# aquam60.net
KiCad netlist of a schematic drawn in EAGLE
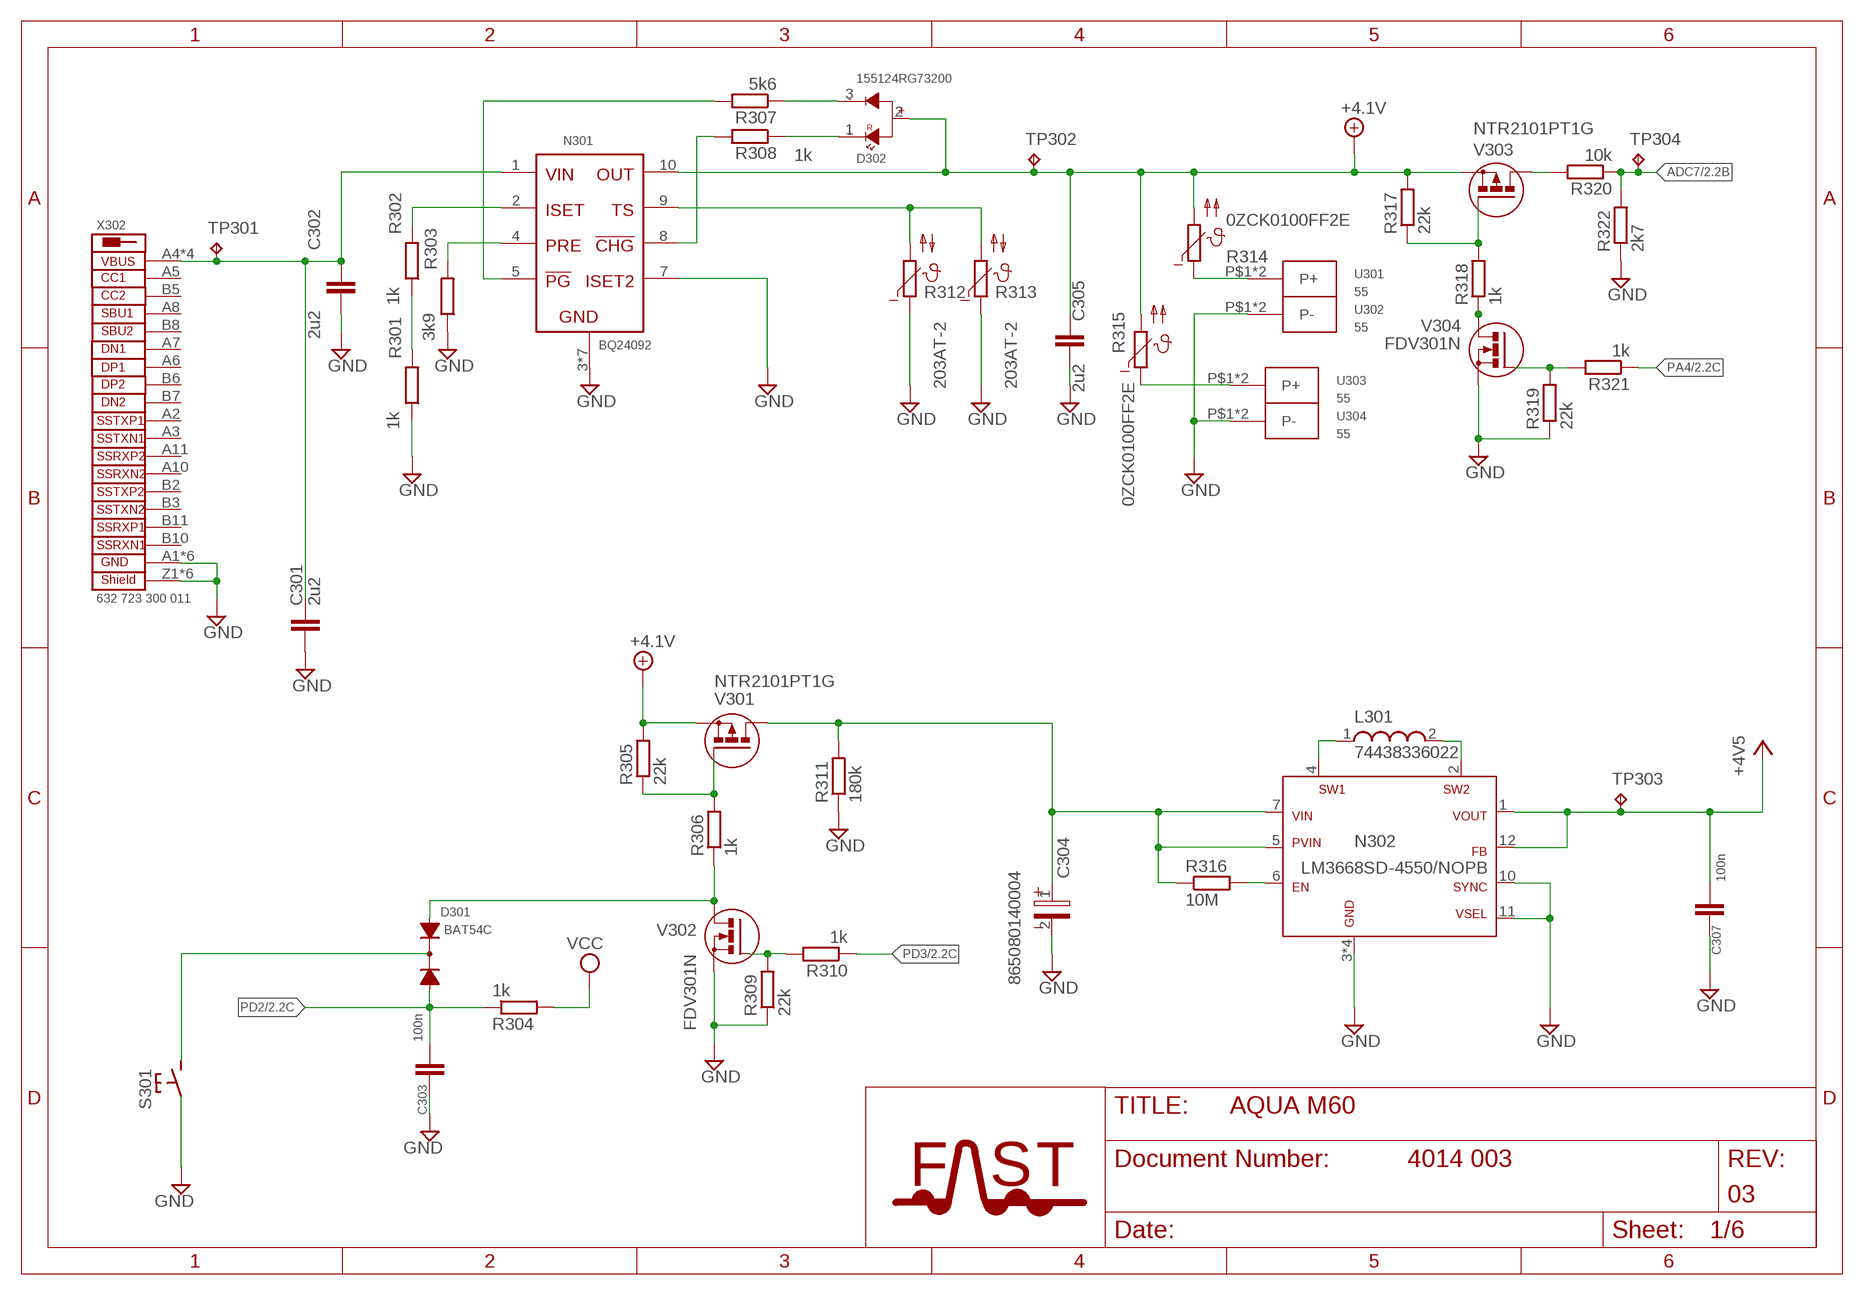
[diagram p0: schematic, sheet 1]
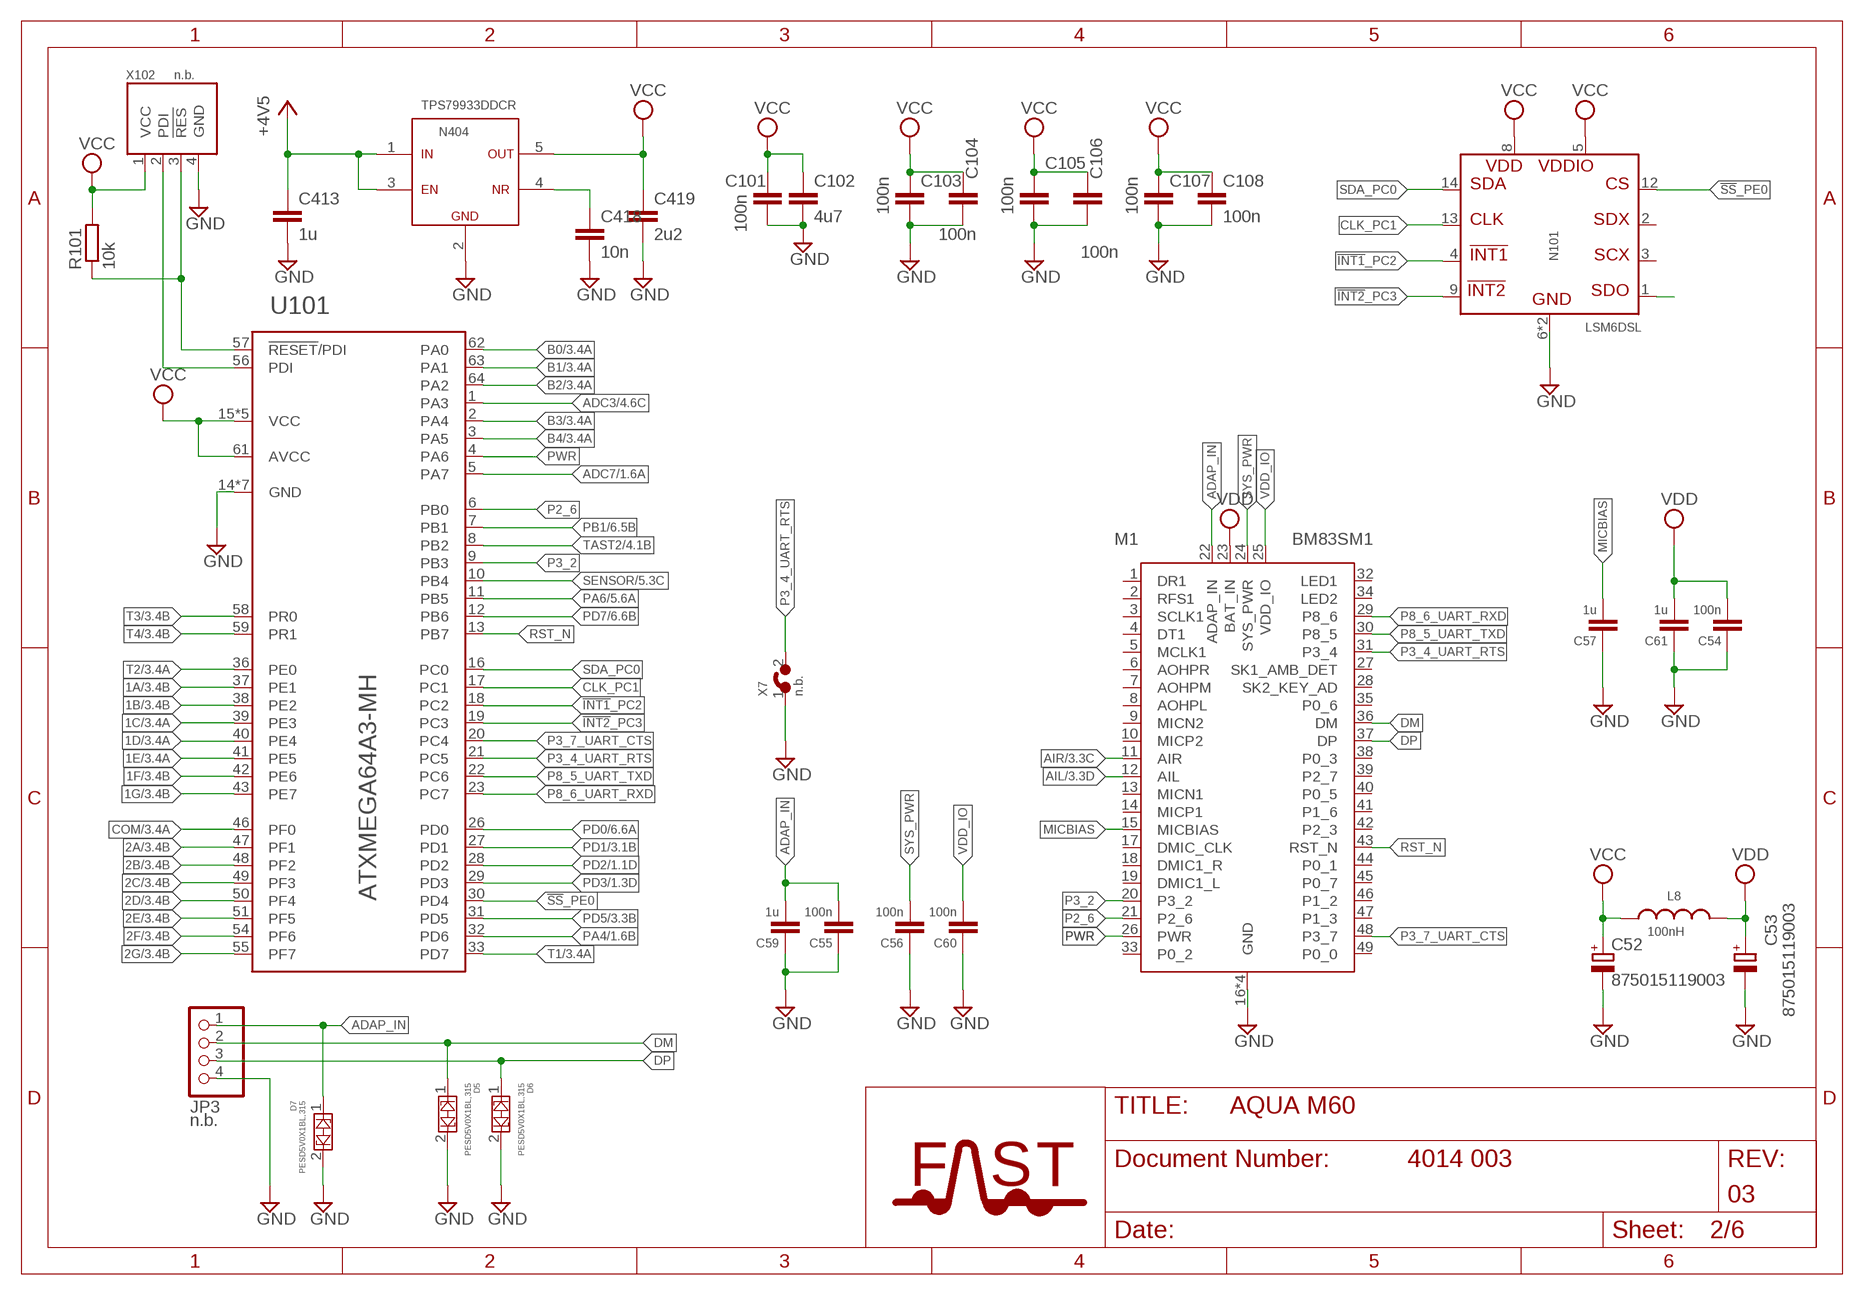
[diagram p1: schematic, sheet 2]
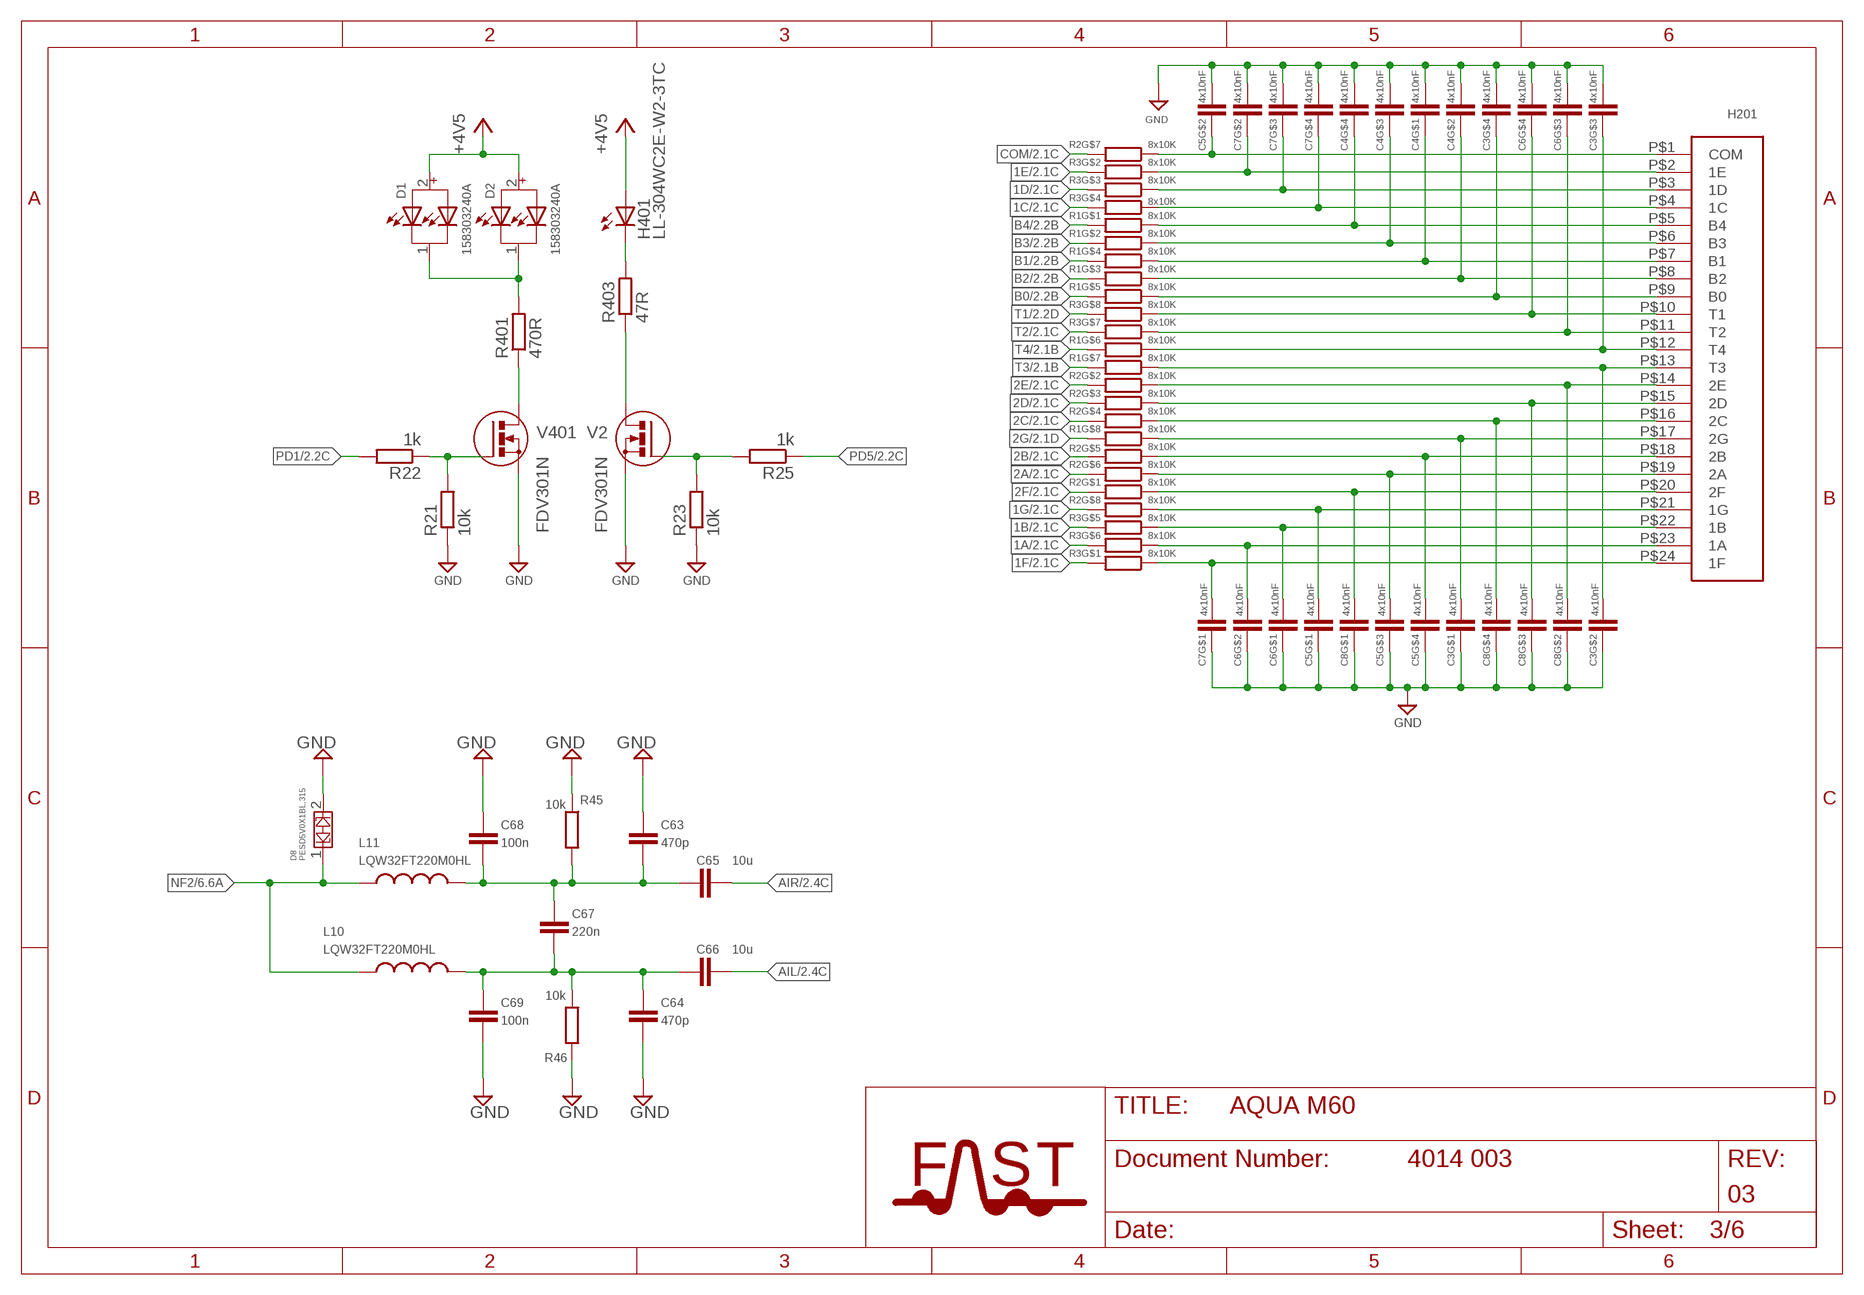
[diagram p2: schematic, sheet 3]
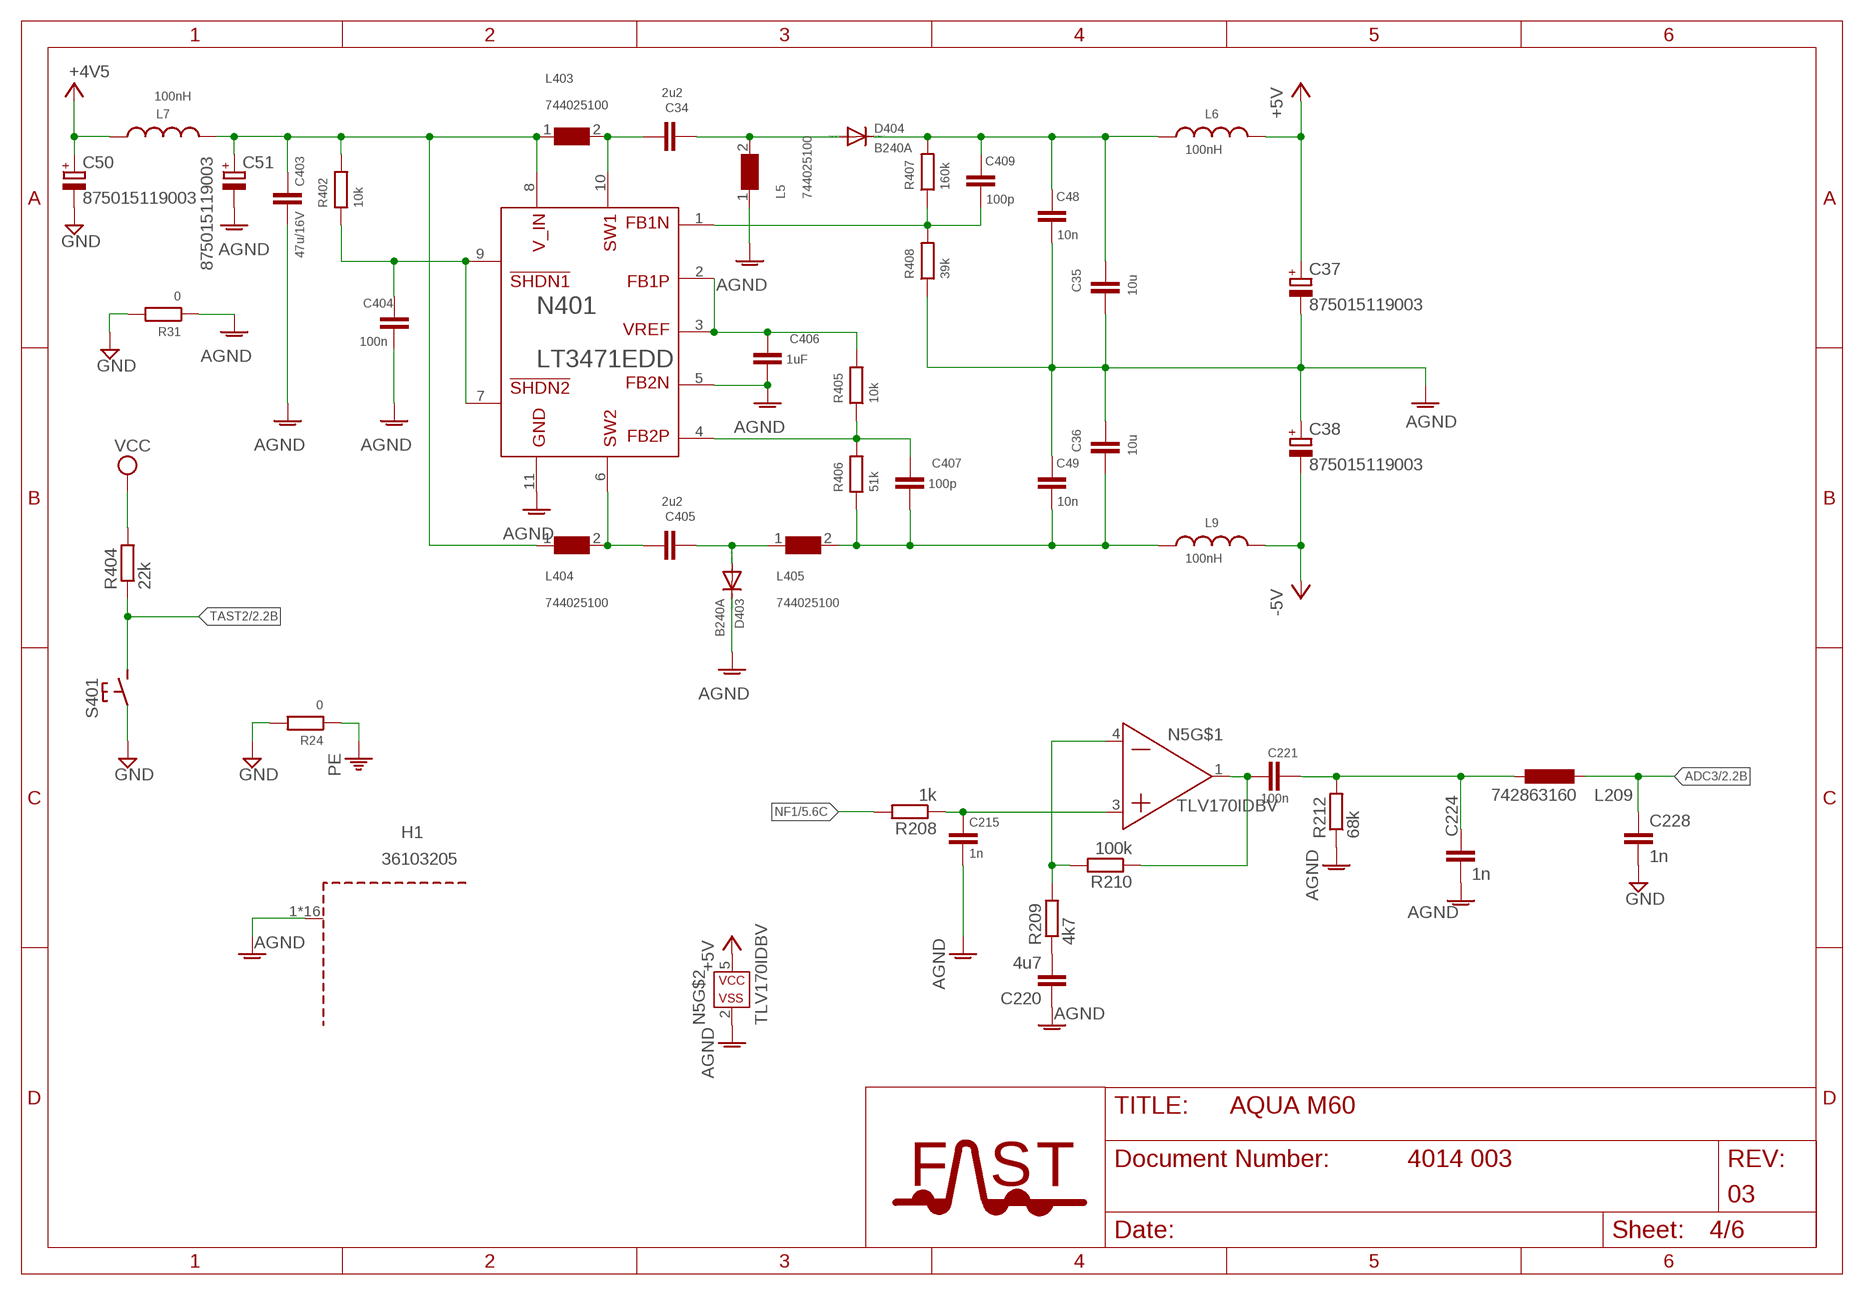
[diagram p3: schematic, sheet 4]
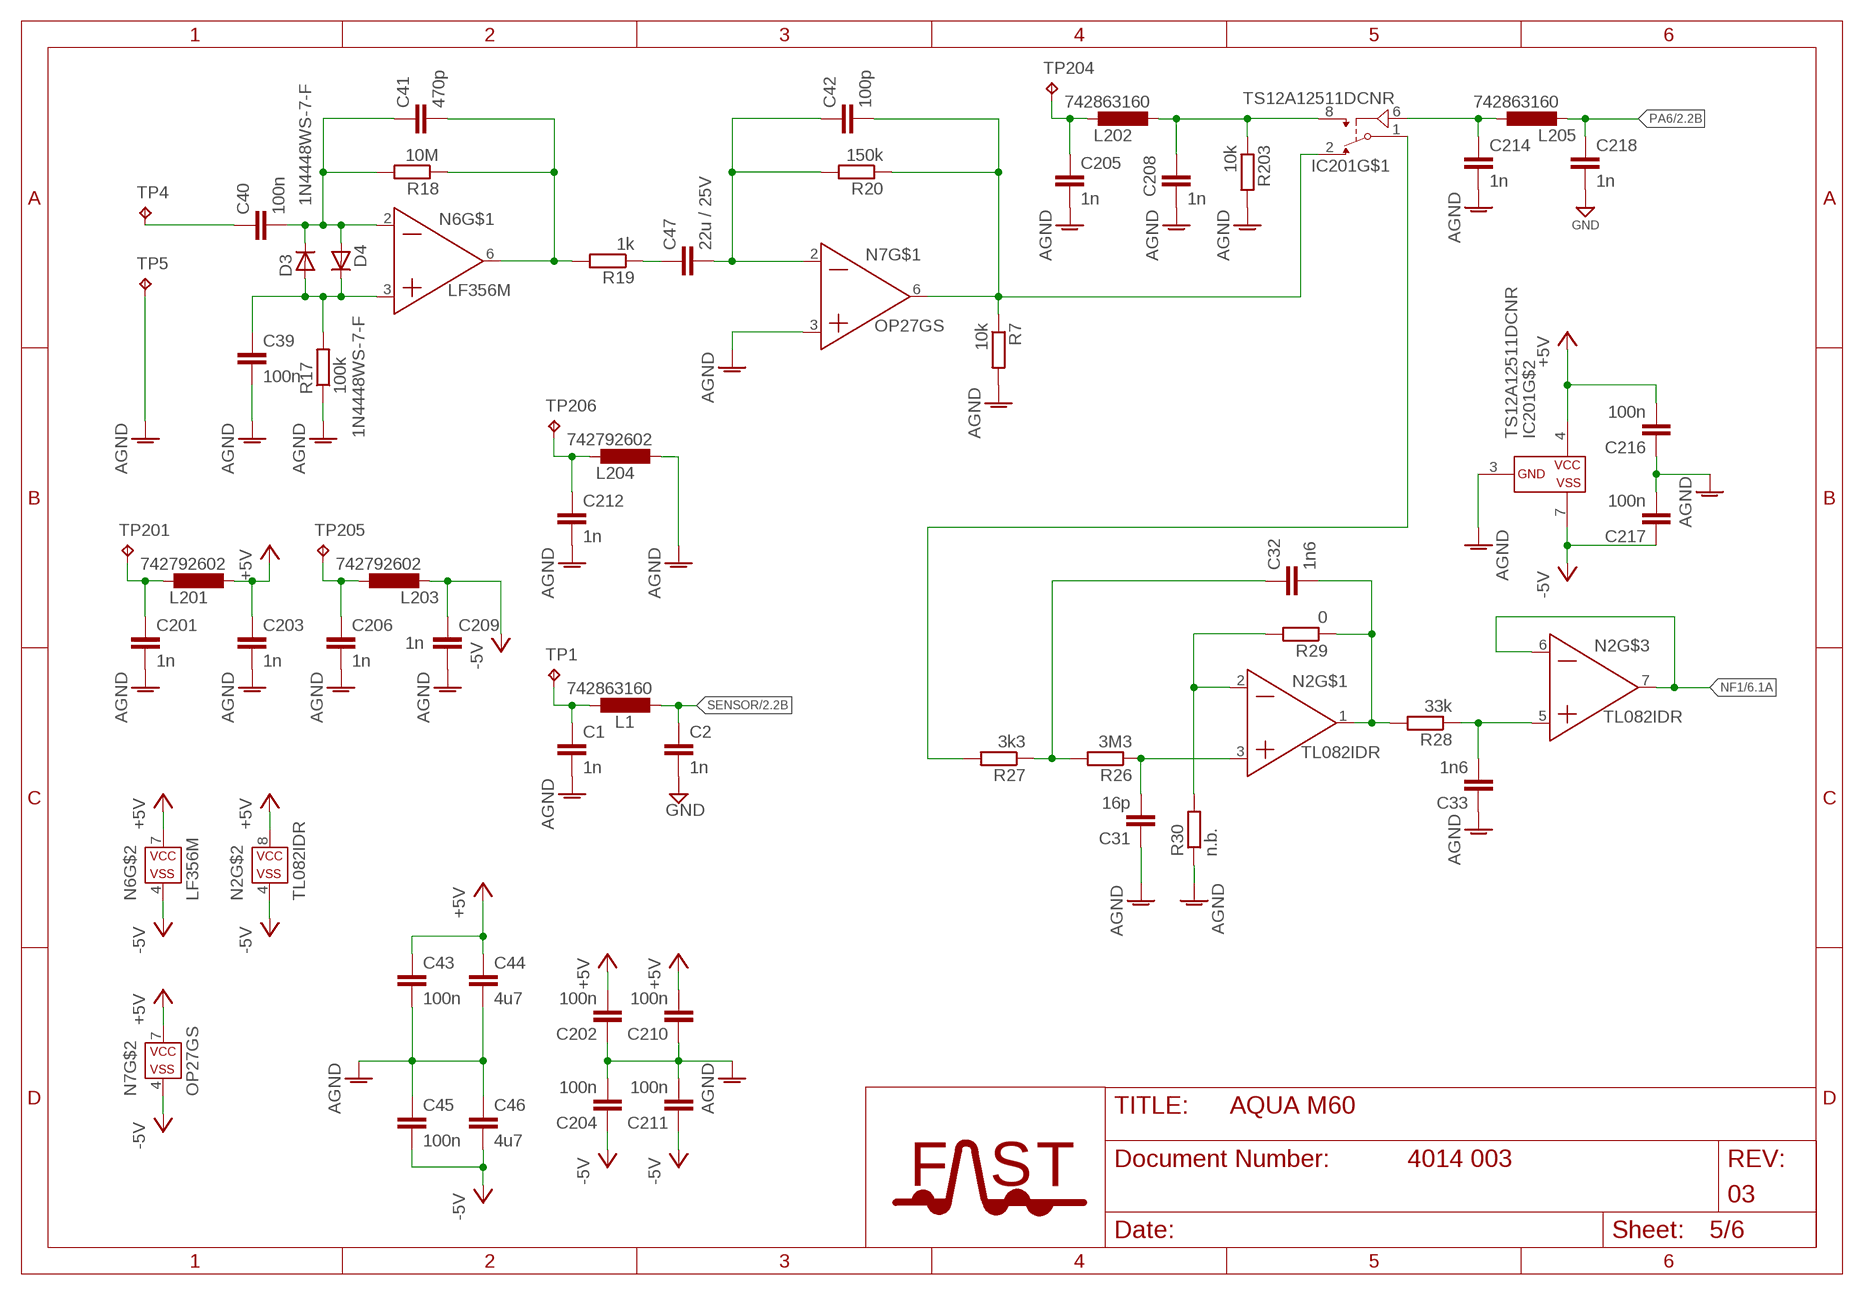
[diagram p4: schematic, sheet 5]
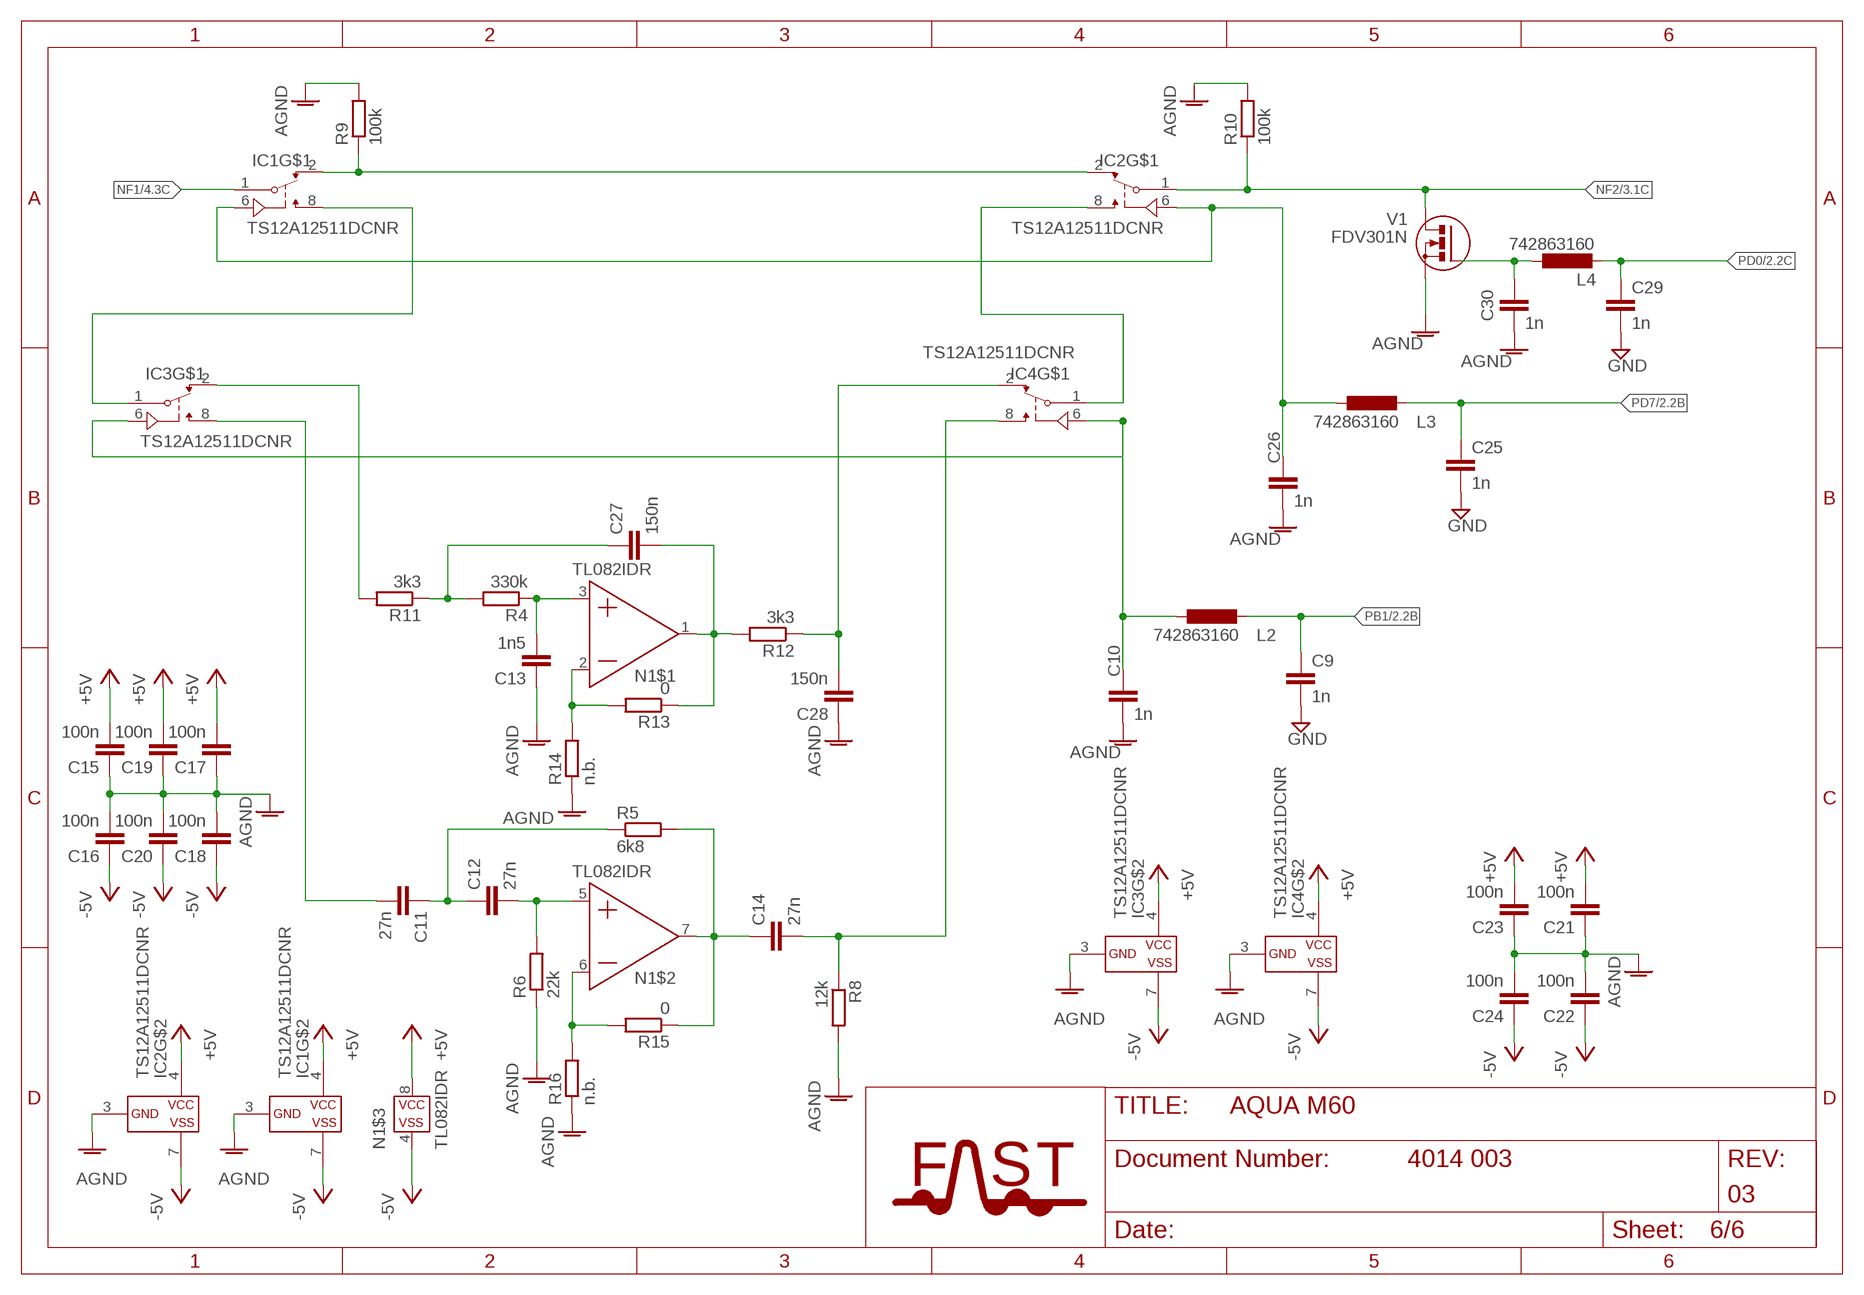
[diagram p5: schematic, sheet 6]

(export (version "E")
  (design (tool "Eeschema 10.0.6"))
  (components
    (comp (ref "C1")
      (value "1n")
      (footprint "eagle-import:C0603")
      (libsource (lib "eagle-import") (part "C-EUC0603"))
    )
    (comp (ref "C2")
      (value "1n")
      (footprint "eagle-import:C0603")
      (libsource (lib "eagle-import") (part "C-EUC0603"))
    )
    (comp (ref "C31")
      (value "16p")
      (footprint "eagle-import:C0603")
      (libsource (lib "eagle-import") (part "C-EUC0603"))
    )
    (comp (ref "C32")
      (value "1n6")
      (footprint "eagle-import:C0603")
      (libsource (lib "eagle-import") (part "C-EUC0603"))
    )
    (comp (ref "C33")
      (value "1n6")
      (footprint "eagle-import:C0603")
      (libsource (lib "eagle-import") (part "C-EUC0603"))
    )
    (comp (ref "C39")
      (value "100n")
      (footprint "eagle-import:C0805")
      (libsource (lib "eagle-import") (part "C-EUC0805"))
    )
    (comp (ref "C40")
      (value "100n")
      (footprint "eagle-import:C0805")
      (libsource (lib "eagle-import") (part "C-EUC0805"))
    )
    (comp (ref "C41")
      (value "470p")
      (footprint "eagle-import:C0805")
      (libsource (lib "eagle-import") (part "C-EUC0805"))
    )
    (comp (ref "C42")
      (value "100p")
      (footprint "eagle-import:C0805")
      (libsource (lib "eagle-import") (part "C-EUC0805"))
    )
    (comp (ref "C43")
      (value "100n")
      (footprint "eagle-import:C0603")
      (libsource (lib "eagle-import") (part "C-EUC0603"))
    )
    (comp (ref "C44")
      (value "4u7")
      (footprint "eagle-import:C0805")
      (libsource (lib "eagle-import") (part "C-EUC0805"))
    )
    (comp (ref "C45")
      (value "100n")
      (footprint "eagle-import:C0603")
      (libsource (lib "eagle-import") (part "C-EUC0603"))
    )
    (comp (ref "C46")
      (value "4u7")
      (footprint "eagle-import:C0805")
      (libsource (lib "eagle-import") (part "C-EUC0805"))
    )
    (comp (ref "C47")
      (value "22u / 25V")
      (footprint "eagle-import:C1210")
      (libsource (lib "eagle-import") (part "C-EUC1210"))
    )
    (comp (ref "C201")
      (value "1n")
      (footprint "eagle-import:C0603")
      (libsource (lib "eagle-import") (part "C-EUC0603"))
    )
    (comp (ref "C202")
      (value "100n")
      (footprint "eagle-import:C0603")
      (libsource (lib "eagle-import") (part "C-EUC0603"))
    )
    (comp (ref "C203")
      (value "1n")
      (footprint "eagle-import:C0603")
      (libsource (lib "eagle-import") (part "C-EUC0603"))
    )
    (comp (ref "C204")
      (value "100n")
      (footprint "eagle-import:C0603")
      (libsource (lib "eagle-import") (part "C-EUC0603"))
    )
    (comp (ref "C205")
      (value "1n")
      (footprint "eagle-import:C0603")
      (libsource (lib "eagle-import") (part "C-EUC0603"))
    )
    (comp (ref "C206")
      (value "1n")
      (footprint "eagle-import:C0603")
      (libsource (lib "eagle-import") (part "C-EUC0603"))
    )
    (comp (ref "C208")
      (value "1n")
      (footprint "eagle-import:C0603")
      (libsource (lib "eagle-import") (part "C-EUC0603"))
    )
    (comp (ref "C209")
      (value "1n")
      (footprint "eagle-import:C0603")
      (libsource (lib "eagle-import") (part "C-EUC0603"))
    )
    (comp (ref "C210")
      (value "100n")
      (footprint "eagle-import:C0603")
      (libsource (lib "eagle-import") (part "C-EUC0603"))
    )
    (comp (ref "C211")
      (value "100n")
      (footprint "eagle-import:C0603")
      (libsource (lib "eagle-import") (part "C-EUC0603"))
    )
    (comp (ref "C212")
      (value "1n")
      (footprint "eagle-import:C0603")
      (libsource (lib "eagle-import") (part "C-EUC0603"))
    )
    (comp (ref "C214")
      (value "1n")
      (footprint "eagle-import:C0603")
      (libsource (lib "eagle-import") (part "C-EUC0603"))
    )
    (comp (ref "C216")
      (value "100n")
      (footprint "eagle-import:C0603")
      (libsource (lib "eagle-import") (part "C-EUC0603"))
    )
    (comp (ref "C217")
      (value "100n")
      (footprint "eagle-import:C0603")
      (libsource (lib "eagle-import") (part "C-EUC0603"))
    )
    (comp (ref "C218")
      (value "1n")
      (footprint "eagle-import:C0603")
      (libsource (lib "eagle-import") (part "C-EUC0603"))
    )
    (comp (ref "D3")
      (value "1N4448WS-7-F")
      (footprint "eagle-import:SOD-323")
      (libsource (lib "eagle-import") (part "1N4448"))
    )
    (comp (ref "D4")
      (value "1N4448WS-7-F")
      (footprint "eagle-import:SOD-323")
      (libsource (lib "eagle-import") (part "1N4448"))
    )
    (comp (ref "IC201")
      (value "TS12A12511DCNR")
      (footprint "eagle-import:SOT-23-8")
      (libsource (lib "eagle-import") (part "TS12A12511DCN"))
    )
    (comp (ref "L1")
      (value "742863160")
      (footprint "eagle-import:R0603")
      (libsource (lib "eagle-import") (part "L-EUR0603"))
    )
    (comp (ref "L201")
      (value "742792602")
      (footprint "eagle-import:R0603")
      (libsource (lib "eagle-import") (part "L-EUR0603"))
    )
    (comp (ref "L202")
      (value "742863160")
      (footprint "eagle-import:R0603")
      (libsource (lib "eagle-import") (part "L-EUR0603"))
    )
    (comp (ref "L203")
      (value "742792602")
      (footprint "eagle-import:R0603")
      (libsource (lib "eagle-import") (part "L-EUR0603"))
    )
    (comp (ref "L204")
      (value "742792602")
      (footprint "eagle-import:R0603")
      (libsource (lib "eagle-import") (part "L-EUR0603"))
    )
    (comp (ref "L205")
      (value "742863160")
      (footprint "eagle-import:R0603")
      (libsource (lib "eagle-import") (part "L-EUR0603"))
    )
    (comp (ref "N2")
      (value "TL082IDR")
      (footprint "eagle-import:SO-8")
      (libsource (lib "eagle-import") (part "OPV_2"))
    )
    (comp (ref "N6")
      (value "LF356M")
      (footprint "eagle-import:SO-8")
      (libsource (lib "eagle-import") (part "OPV_1"))
    )
    (comp (ref "N7")
      (value "OP27GS")
      (footprint "eagle-import:SO-8")
      (libsource (lib "eagle-import") (part "OPV_1"))
    )
    (comp (ref "R7")
      (value "10k")
      (footprint "eagle-import:R0603")
      (libsource (lib "eagle-import") (part "R-EU_R0603"))
    )
    (comp (ref "R17")
      (value "100k")
      (footprint "eagle-import:R0805")
      (libsource (lib "eagle-import") (part "R-EU_R0805"))
    )
    (comp (ref "R18")
      (value "10M")
      (footprint "eagle-import:R0805")
      (libsource (lib "eagle-import") (part "R-EU_R0805"))
    )
    (comp (ref "R19")
      (value "1k")
      (footprint "eagle-import:R0805")
      (libsource (lib "eagle-import") (part "R-EU_R0805"))
    )
    (comp (ref "R20")
      (value "150k")
      (footprint "eagle-import:R0805")
      (libsource (lib "eagle-import") (part "R-EU_R0805"))
    )
    (comp (ref "R26")
      (value "3M3")
      (footprint "eagle-import:R0603")
      (libsource (lib "eagle-import") (part "R-EU_R0603"))
    )
    (comp (ref "R27")
      (value "3k3")
      (footprint "eagle-import:R0603")
      (libsource (lib "eagle-import") (part "R-EU_R0603"))
    )
    (comp (ref "R28")
      (value "33k")
      (footprint "eagle-import:R0603")
      (libsource (lib "eagle-import") (part "R-EU_R0603"))
    )
    (comp (ref "R29")
      (value "0")
      (footprint "eagle-import:R0603")
      (libsource (lib "eagle-import") (part "R-EU_R0603"))
    )
    (comp (ref "R30")
      (value "n.b.")
      (footprint "eagle-import:R0603")
      (libsource (lib "eagle-import") (part "R-EU_R0603"))
    )
    (comp (ref "R203")
      (value "10k")
      (footprint "eagle-import:R0603")
      (libsource (lib "eagle-import") (part "R-EU_R0603"))
    )
    (comp (ref "TP1")
      (value "n.b.")
      (footprint "eagle-import:P1-08")
      (libsource (lib "eagle-import") (part "TPB0,80"))
    )
    (comp (ref "TP4")
      (value "n.b.")
      (footprint "eagle-import:P1-13R")
      (libsource (lib "eagle-import") (part "TPPAD1-13R"))
    )
    (comp (ref "TP5")
      (value "n.b.")
      (footprint "eagle-import:P1-20")
      (libsource (lib "eagle-import") (part "TPPAD1-20"))
    )
    (comp (ref "TP201")
      (value "n.b.")
      (footprint "eagle-import:P1-08")
      (libsource (lib "eagle-import") (part "TPB0,80"))
    )
    (comp (ref "TP204")
      (value "n.b.")
      (footprint "eagle-import:P1-08")
      (libsource (lib "eagle-import") (part "TPB0,80"))
    )
    (comp (ref "TP205")
      (value "n.b.")
      (footprint "eagle-import:P1-08")
      (libsource (lib "eagle-import") (part "TPB0,80"))
    )
    (comp (ref "TP206")
      (value "n.b.")
      (footprint "eagle-import:P1-08")
      (libsource (lib "eagle-import") (part "TPB0,80"))
    )
    (comp (ref "C301")
      (value "2u2")
      (footprint "eagle-import:C0603")
      (libsource (lib "eagle-import") (part "C-EUC0603"))
    )
    (comp (ref "C302")
      (value "2u2")
      (footprint "eagle-import:C0603")
      (libsource (lib "eagle-import") (part "C-EUC0603"))
    )
    (comp (ref "C303")
      (value "100n")
      (footprint "eagle-import:C0603")
      (libsource (lib "eagle-import") (part "C-EUC0603"))
    )
    (comp (ref "C304")
      (value "865080140004")
      (footprint "eagle-import:2.6X1.6X1(BXCXA)")
      (libsource (lib "eagle-import") (part "WCAP-ASLI_4X5.5(DXL)"))
    )
    (comp (ref "C305")
      (value "2u2")
      (footprint "eagle-import:C0603")
      (libsource (lib "eagle-import") (part "C-EUC0603"))
    )
    (comp (ref "C307")
      (value "100n")
      (footprint "eagle-import:C0603")
      (libsource (lib "eagle-import") (part "C-EUC0603"))
    )
    (comp (ref "D301")
      (value "BAT54C")
      (footprint "eagle-import:SOT23")
      (libsource (lib "eagle-import") (part "BAT54C-1"))
    )
    (comp (ref "D302")
      (value "155124RG73200")
      (footprint "eagle-import:WL-SBSW_1204")
      (libsource (lib "eagle-import") (part "WL-SBSW_1204_155124RG73200"))
    )
    (comp (ref "L301")
      (value "74438336022")
      (footprint "eagle-import:WE-MAPI_3015_3020")
      (libsource (lib "eagle-import") (part "WE-MAPI_3015/3020_STANDER"))
    )
    (comp (ref "N301")
      (value "BQ24092")
      (footprint "eagle-import:HVSSOP10")
      (libsource (lib "eagle-import") (part "BQ2409X"))
    )
    (comp (ref "N302")
      (value "LM3668SD-4550/NOPB")
      (footprint "eagle-import:DFN_12POL_+0,2MM")
      (libsource (lib "eagle-import") (part "LM3668SD"))
    )
    (comp (ref "R301")
      (value "1k")
      (footprint "eagle-import:R0603")
      (libsource (lib "eagle-import") (part "R-EU_R0603"))
    )
    (comp (ref "R302")
      (value "1k")
      (footprint "eagle-import:R0603")
      (libsource (lib "eagle-import") (part "R-EU_R0603"))
    )
    (comp (ref "R303")
      (value "3k9")
      (footprint "eagle-import:R0603")
      (libsource (lib "eagle-import") (part "R-EU_R0603"))
    )
    (comp (ref "R304")
      (value "1k")
      (footprint "eagle-import:R0603")
      (libsource (lib "eagle-import") (part "R-EU_R0603"))
    )
    (comp (ref "R305")
      (value "22k")
      (footprint "eagle-import:R0603")
      (libsource (lib "eagle-import") (part "R-EU_R0603"))
    )
    (comp (ref "R306")
      (value "1k")
      (footprint "eagle-import:R0603")
      (libsource (lib "eagle-import") (part "R-EU_R0603"))
    )
    (comp (ref "R307")
      (value "5k6")
      (footprint "eagle-import:R0603")
      (libsource (lib "eagle-import") (part "R-EU_R0603"))
    )
    (comp (ref "R308")
      (value "1k")
      (footprint "eagle-import:R0603")
      (libsource (lib "eagle-import") (part "R-EU_R0603"))
    )
    (comp (ref "R309")
      (value "22k")
      (footprint "eagle-import:R0603")
      (libsource (lib "eagle-import") (part "R-EU_R0603"))
    )
    (comp (ref "R310")
      (value "1k")
      (footprint "eagle-import:R0603")
      (libsource (lib "eagle-import") (part "R-EU_R0603"))
    )
    (comp (ref "R311")
      (value "180k")
      (footprint "eagle-import:R0603")
      (libsource (lib "eagle-import") (part "R-EU_R0603"))
    )
    (comp (ref "R312")
      (value "203AT-2")
      (footprint "eagle-import:AT-2")
      (libsource (lib "eagle-import") (part "NTC"))
    )
    (comp (ref "R313")
      (value "203AT-2")
      (footprint "eagle-import:AT-2")
      (libsource (lib "eagle-import") (part "NTC"))
    )
    (comp (ref "R314")
      (value "0ZCK0100FF2E")
      (footprint "eagle-import:R0805")
      (libsource (lib "eagle-import") (part "PTC"))
    )
    (comp (ref "R315")
      (value "0ZCK0100FF2E")
      (footprint "eagle-import:R0805")
      (libsource (lib "eagle-import") (part "PTC"))
    )
    (comp (ref "R316")
      (value "10M")
      (footprint "eagle-import:R0603")
      (libsource (lib "eagle-import") (part "R-EU_R0603"))
    )
    (comp (ref "R317")
      (value "22k")
      (footprint "eagle-import:R0603")
      (libsource (lib "eagle-import") (part "R-EU_R0603"))
    )
    (comp (ref "R318")
      (value "1k")
      (footprint "eagle-import:R0603")
      (libsource (lib "eagle-import") (part "R-EU_R0603"))
    )
    (comp (ref "R319")
      (value "22k")
      (footprint "eagle-import:R0603")
      (libsource (lib "eagle-import") (part "R-EU_R0603"))
    )
    (comp (ref "R320")
      (value "10k")
      (footprint "eagle-import:R0603")
      (libsource (lib "eagle-import") (part "R-EU_R0603"))
    )
    (comp (ref "R321")
      (value "1k")
      (footprint "eagle-import:R0603")
      (libsource (lib "eagle-import") (part "R-EU_R0603"))
    )
    (comp (ref "R322")
      (value "2k7")
      (footprint "eagle-import:R0603")
      (libsource (lib "eagle-import") (part "R-EU_R0603"))
    )
    (comp (ref "S301")
      (value "1301.9320")
      (footprint "eagle-import:1301.93XX")
      (libsource (lib "eagle-import") (part "1301.93XX"))
    )
    (comp (ref "TP301")
      (value "n.b.")
      (footprint "eagle-import:TP10R")
      (libsource (lib "eagle-import") (part "TPTP10R"))
    )
    (comp (ref "TP302")
      (value "n.b.")
      (footprint "eagle-import:TP10R")
      (libsource (lib "eagle-import") (part "TPTP10R"))
    )
    (comp (ref "TP303")
      (value "n.b.")
      (footprint "eagle-import:TP10R")
      (libsource (lib "eagle-import") (part "TPTP10R"))
    )
    (comp (ref "TP304")
      (value "n.b.")
      (footprint "eagle-import:TP10R")
      (libsource (lib "eagle-import") (part "TPTP10R"))
    )
    (comp (ref "U301")
      (value "55")
      (footprint "eagle-import:55+")
      (libsource (lib "eagle-import") (part "55+"))
    )
    (comp (ref "U302")
      (value "55")
      (footprint "eagle-import:55-")
      (libsource (lib "eagle-import") (part "55--"))
    )
    (comp (ref "U303")
      (value "55")
      (footprint "eagle-import:55+")
      (libsource (lib "eagle-import") (part "55+"))
    )
    (comp (ref "U304")
      (value "55")
      (footprint "eagle-import:55-")
      (libsource (lib "eagle-import") (part "55--"))
    )
    (comp (ref "V301")
      (value "NTR2101PT1G")
      (footprint "eagle-import:SMDTR-1")
      (libsource (lib "eagle-import") (part "P-MOSFET-SOT23"))
    )
    (comp (ref "V302")
      (value "FDV301N")
      (footprint "eagle-import:SMDTR-1")
      (libsource (lib "eagle-import") (part "N-MOSFET-SOT23"))
    )
    (comp (ref "V303")
      (value "NTR2101PT1G")
      (footprint "eagle-import:SMDTR-1")
      (libsource (lib "eagle-import") (part "P-MOSFET-SOT23"))
    )
    (comp (ref "V304")
      (value "FDV301N")
      (footprint "eagle-import:SMDTR-1")
      (libsource (lib "eagle-import") (part "N-MOSFET-SOT23"))
    )
    (comp (ref "X302")
      (value "632 723 300 011")
      (footprint "eagle-import:632723300011_4L")
      (libsource (lib "eagle-import") (part "USB_3.1_TYPE_C_4L"))
    )
    (comp (ref "C3")
      (value "4x10nF")
      (footprint "eagle-import:C0612")
      (libsource (lib "eagle-import") (part "C_ARRAY_4X"))
    )
    (comp (ref "C4")
      (value "4x10nF")
      (footprint "eagle-import:C0612")
      (libsource (lib "eagle-import") (part "C_ARRAY_4X"))
    )
    (comp (ref "C5")
      (value "4x10nF")
      (footprint "eagle-import:C0612")
      (libsource (lib "eagle-import") (part "C_ARRAY_4X"))
    )
    (comp (ref "C6")
      (value "4x10nF")
      (footprint "eagle-import:C0612")
      (libsource (lib "eagle-import") (part "C_ARRAY_4X"))
    )
    (comp (ref "C7")
      (value "4x10nF")
      (footprint "eagle-import:C0612")
      (libsource (lib "eagle-import") (part "C_ARRAY_4X"))
    )
    (comp (ref "C8")
      (value "4x10nF")
      (footprint "eagle-import:C0612")
      (libsource (lib "eagle-import") (part "C_ARRAY_4X"))
    )
    (comp (ref "C63")
      (value "470p")
      (footprint "eagle-import:C0603")
      (libsource (lib "eagle-import") (part "C-EUC0603"))
    )
    (comp (ref "C64")
      (value "470p")
      (footprint "eagle-import:C0603")
      (libsource (lib "eagle-import") (part "C-EUC0603"))
    )
    (comp (ref "C65")
      (value "10u")
      (footprint "eagle-import:C0805")
      (libsource (lib "eagle-import") (part "C-EUC0805"))
    )
    (comp (ref "C66")
      (value "10u")
      (footprint "eagle-import:C0805")
      (libsource (lib "eagle-import") (part "C-EUC0805"))
    )
    (comp (ref "C67")
      (value "220n")
      (footprint "eagle-import:C0603")
      (libsource (lib "eagle-import") (part "C-EUC0603"))
    )
    (comp (ref "C68")
      (value "100n")
      (footprint "eagle-import:C0603")
      (libsource (lib "eagle-import") (part "C-EUC0603"))
    )
    (comp (ref "C69")
      (value "100n")
      (footprint "eagle-import:C0603")
      (libsource (lib "eagle-import") (part "C-EUC0603"))
    )
    (comp (ref "D1")
      (value "158303240A")
      (footprint "eagle-import:WL-SWTP_3030")
      (libsource (lib "eagle-import") (part "WL-SWTP_3030_158303240A"))
    )
    (comp (ref "D2")
      (value "158303240A")
      (footprint "eagle-import:WL-SWTP_3030")
      (libsource (lib "eagle-import") (part "WL-SWTP_3030_158303240A"))
    )
    (comp (ref "D8")
      (value "PESD5V0X1BL,315")
      (footprint "eagle-import:DIODFN100X60X60-2")
      (libsource (lib "eagle-import") (part "PESD5V0X1BL,315"))
    )
    (comp (ref "H201")
      (value "AQUAM60")
      (footprint "eagle-import:AQUAM60")
      (libsource (lib "eagle-import") (part "AQUAM60"))
    )
    (comp (ref "H401")
      (value "LL-304WC2E-W2-3TC")
      (footprint "eagle-import:LED3MM_H7,5MM")
      (libsource (lib "eagle-import") (part "LED"))
    )
    (comp (ref "L10")
      (value "LQW32FT220M0HL")
      (footprint "eagle-import:INDC3225X250N")
      (fields (field (name "MF") "Murata"))
      (libsource (lib "eagle-import") (part "LQW32FT220M0HL"))
    )
    (comp (ref "L11")
      (value "LQW32FT220M0HL")
      (footprint "eagle-import:INDC3225X250N")
      (fields (field (name "MF") "Murata"))
      (libsource (lib "eagle-import") (part "LQW32FT220M0HL"))
    )
    (comp (ref "R1")
      (value "8x10K")
      (footprint "eagle-import:R1506")
      (libsource (lib "eagle-import") (part "R_ARRAY_8X"))
    )
    (comp (ref "R2")
      (value "8x10K")
      (footprint "eagle-import:R1506")
      (libsource (lib "eagle-import") (part "R_ARRAY_8X"))
    )
    (comp (ref "R3")
      (value "8x10K")
      (footprint "eagle-import:R1506")
      (libsource (lib "eagle-import") (part "R_ARRAY_8X"))
    )
    (comp (ref "R21")
      (value "10k")
      (footprint "eagle-import:R0603")
      (libsource (lib "eagle-import") (part "R-EU_R0603"))
    )
    (comp (ref "R22")
      (value "1k")
      (footprint "eagle-import:R0603")
      (libsource (lib "eagle-import") (part "R-EU_R0603"))
    )
    (comp (ref "R23")
      (value "10k")
      (footprint "eagle-import:R0603")
      (libsource (lib "eagle-import") (part "R-EU_R0603"))
    )
    (comp (ref "R25")
      (value "1k")
      (footprint "eagle-import:R0603")
      (libsource (lib "eagle-import") (part "R-EU_R0603"))
    )
    (comp (ref "R45")
      (value "10k")
      (footprint "eagle-import:R0603")
      (libsource (lib "eagle-import") (part "R-EU_R0603"))
    )
    (comp (ref "R46")
      (value "10k")
      (footprint "eagle-import:R0603")
      (libsource (lib "eagle-import") (part "R-EU_R0603"))
    )
    (comp (ref "R401")
      (value "470R")
      (footprint "eagle-import:R0805")
      (libsource (lib "eagle-import") (part "R-EU_R0805"))
    )
    (comp (ref "R403")
      (value "47R")
      (footprint "eagle-import:R0805")
      (libsource (lib "eagle-import") (part "R-EU_R0805"))
    )
    (comp (ref "V2")
      (value "FDV301N")
      (footprint "eagle-import:SMDTR-1")
      (libsource (lib "eagle-import") (part "N-MOSFET-SOT23"))
    )
    (comp (ref "V401")
      (value "FDV301N")
      (footprint "eagle-import:SMDTR-1")
      (libsource (lib "eagle-import") (part "N-MOSFET-SOT23"))
    )
    (comp (ref "C9")
      (value "1n")
      (footprint "eagle-import:C0603")
      (libsource (lib "eagle-import") (part "C-EUC0603"))
    )
    (comp (ref "C10")
      (value "1n")
      (footprint "eagle-import:C0603")
      (libsource (lib "eagle-import") (part "C-EUC0603"))
    )
    (comp (ref "C11")
      (value "27n")
      (footprint "eagle-import:C0603")
      (libsource (lib "eagle-import") (part "C-EUC0603"))
    )
    (comp (ref "C12")
      (value "27n")
      (footprint "eagle-import:C0603")
      (libsource (lib "eagle-import") (part "C-EUC0603"))
    )
    (comp (ref "C13")
      (value "1n5")
      (footprint "eagle-import:C0603")
      (libsource (lib "eagle-import") (part "C-EUC0603"))
    )
    (comp (ref "C14")
      (value "27n")
      (footprint "eagle-import:C0603")
      (libsource (lib "eagle-import") (part "C-EUC0603"))
    )
    (comp (ref "C15")
      (value "100n")
      (footprint "eagle-import:C0603")
      (libsource (lib "eagle-import") (part "C-EUC0603"))
    )
    (comp (ref "C16")
      (value "100n")
      (footprint "eagle-import:C0603")
      (libsource (lib "eagle-import") (part "C-EUC0603"))
    )
    (comp (ref "C17")
      (value "100n")
      (footprint "eagle-import:C0603")
      (libsource (lib "eagle-import") (part "C-EUC0603"))
    )
    (comp (ref "C18")
      (value "100n")
      (footprint "eagle-import:C0603")
      (libsource (lib "eagle-import") (part "C-EUC0603"))
    )
    (comp (ref "C19")
      (value "100n")
      (footprint "eagle-import:C0603")
      (libsource (lib "eagle-import") (part "C-EUC0603"))
    )
    (comp (ref "C20")
      (value "100n")
      (footprint "eagle-import:C0603")
      (libsource (lib "eagle-import") (part "C-EUC0603"))
    )
    (comp (ref "C21")
      (value "100n")
      (footprint "eagle-import:C0603")
      (libsource (lib "eagle-import") (part "C-EUC0603"))
    )
    (comp (ref "C22")
      (value "100n")
      (footprint "eagle-import:C0603")
      (libsource (lib "eagle-import") (part "C-EUC0603"))
    )
    (comp (ref "C23")
      (value "100n")
      (footprint "eagle-import:C0603")
      (libsource (lib "eagle-import") (part "C-EUC0603"))
    )
    (comp (ref "C24")
      (value "100n")
      (footprint "eagle-import:C0603")
      (libsource (lib "eagle-import") (part "C-EUC0603"))
    )
    (comp (ref "C25")
      (value "1n")
      (footprint "eagle-import:C0603")
      (libsource (lib "eagle-import") (part "C-EUC0603"))
    )
    (comp (ref "C26")
      (value "1n")
      (footprint "eagle-import:C0603")
      (libsource (lib "eagle-import") (part "C-EUC0603"))
    )
    (comp (ref "C27")
      (value "150n")
      (footprint "eagle-import:C0603")
      (libsource (lib "eagle-import") (part "C-EUC0603"))
    )
    (comp (ref "C28")
      (value "150n")
      (footprint "eagle-import:C0603")
      (libsource (lib "eagle-import") (part "C-EUC0603"))
    )
    (comp (ref "C29")
      (value "1n")
      (footprint "eagle-import:C0603")
      (libsource (lib "eagle-import") (part "C-EUC0603"))
    )
    (comp (ref "C30")
      (value "1n")
      (footprint "eagle-import:C0603")
      (libsource (lib "eagle-import") (part "C-EUC0603"))
    )
    (comp (ref "IC1")
      (value "TS12A12511DCNR")
      (footprint "eagle-import:SOT-23-8")
      (libsource (lib "eagle-import") (part "TS12A12511DCN"))
    )
    (comp (ref "IC2")
      (value "TS12A12511DCNR")
      (footprint "eagle-import:SOT-23-8")
      (libsource (lib "eagle-import") (part "TS12A12511DCN"))
    )
    (comp (ref "IC3")
      (value "TS12A12511DCNR")
      (footprint "eagle-import:SOT-23-8")
      (libsource (lib "eagle-import") (part "TS12A12511DCN"))
    )
    (comp (ref "IC4")
      (value "TS12A12511DCNR")
      (footprint "eagle-import:SOT-23-8")
      (libsource (lib "eagle-import") (part "TS12A12511DCN"))
    )
    (comp (ref "L2")
      (value "742863160")
      (footprint "eagle-import:R0603")
      (libsource (lib "eagle-import") (part "L-EUR0603"))
    )
    (comp (ref "L3")
      (value "742863160")
      (footprint "eagle-import:R0603")
      (libsource (lib "eagle-import") (part "L-EUR0603"))
    )
    (comp (ref "L4")
      (value "742863160")
      (footprint "eagle-import:R0603")
      (libsource (lib "eagle-import") (part "L-EUR0603"))
    )
    (comp (ref "N1")
      (value "TL082IDR")
      (footprint "eagle-import:SO-8")
      (libsource (lib "eagle-import") (part "MCP6V02"))
    )
    (comp (ref "R4")
      (value "330k")
      (footprint "eagle-import:R0603")
      (libsource (lib "eagle-import") (part "R-EU_R0603"))
    )
    (comp (ref "R5")
      (value "6k8")
      (footprint "eagle-import:R0603")
      (libsource (lib "eagle-import") (part "R-EU_R0603"))
    )
    (comp (ref "R6")
      (value "22k")
      (footprint "eagle-import:R0603")
      (libsource (lib "eagle-import") (part "R-EU_R0603"))
    )
    (comp (ref "R8")
      (value "12k")
      (footprint "eagle-import:R0603")
      (libsource (lib "eagle-import") (part "R-EU_R0603"))
    )
    (comp (ref "R9")
      (value "100k")
      (footprint "eagle-import:R0603")
      (libsource (lib "eagle-import") (part "R-EU_R0603"))
    )
    (comp (ref "R10")
      (value "100k")
      (footprint "eagle-import:R0603")
      (libsource (lib "eagle-import") (part "R-EU_R0603"))
    )
    (comp (ref "R11")
      (value "3k3")
      (footprint "eagle-import:R0603")
      (libsource (lib "eagle-import") (part "R-EU_R0603"))
    )
    (comp (ref "R12")
      (value "3k3")
      (footprint "eagle-import:R0603")
      (libsource (lib "eagle-import") (part "R-EU_R0603"))
    )
    (comp (ref "R13")
      (value "0")
      (footprint "eagle-import:R0603")
      (libsource (lib "eagle-import") (part "R-EU_R0603"))
    )
    (comp (ref "R14")
      (value "n.b.")
      (footprint "eagle-import:R0603")
      (libsource (lib "eagle-import") (part "R-EU_R0603"))
    )
    (comp (ref "R15")
      (value "0")
      (footprint "eagle-import:R0603")
      (libsource (lib "eagle-import") (part "R-EU_R0603"))
    )
    (comp (ref "R16")
      (value "n.b.")
      (footprint "eagle-import:R0603")
      (libsource (lib "eagle-import") (part "R-EU_R0603"))
    )
    (comp (ref "V1")
      (value "FDV301N")
      (footprint "eagle-import:SMDTR-1")
      (libsource (lib "eagle-import") (part "N-MOSFET-SOT23"))
    )
    (comp (ref "C34")
      (value "2u2")
      (footprint "eagle-import:C0603")
      (libsource (lib "eagle-import") (part "C-EUC0603"))
    )
    (comp (ref "C35")
      (value "10u")
      (footprint "eagle-import:C1210")
      (libsource (lib "eagle-import") (part "C-EUC1210"))
    )
    (comp (ref "C36")
      (value "10u")
      (footprint "eagle-import:C1210")
      (libsource (lib "eagle-import") (part "C-EUC1210"))
    )
    (comp (ref "C37")
      (value "875015119003")
      (footprint "eagle-import:WE_WCAP-PHGP")
      (libsource (lib "eagle-import") (part "KONDENSATOR_WE_WCAP_PHET_7,3X4,3X1,9MM"))
    )
    (comp (ref "C38")
      (value "875015119003")
      (footprint "eagle-import:WE_WCAP-PHGP")
      (libsource (lib "eagle-import") (part "KONDENSATOR_WE_WCAP_PHET_7,3X4,3X1,9MM"))
    )
    (comp (ref "C48")
      (value "10n")
      (footprint "eagle-import:C0603")
      (libsource (lib "eagle-import") (part "C-EUC0603"))
    )
    (comp (ref "C49")
      (value "10n")
      (footprint "eagle-import:C0603")
      (libsource (lib "eagle-import") (part "C-EUC0603"))
    )
    (comp (ref "C50")
      (value "875015119003")
      (footprint "eagle-import:WE_WCAP-PHGP")
      (libsource (lib "eagle-import") (part "KONDENSATOR_WE_WCAP_PHET_7,3X4,3X1,9MM"))
    )
    (comp (ref "C51")
      (value "875015119003")
      (footprint "eagle-import:WE_WCAP-PHGP")
      (libsource (lib "eagle-import") (part "KONDENSATOR_WE_WCAP_PHET_7,3X4,3X1,9MM"))
    )
    (comp (ref "C215")
      (value "1n")
      (footprint "eagle-import:C0603")
      (libsource (lib "eagle-import") (part "C-EUC0603"))
    )
    (comp (ref "C220")
      (value "4u7")
      (footprint "eagle-import:C0805")
      (libsource (lib "eagle-import") (part "C-EUC0805"))
    )
    (comp (ref "C221")
      (value "100n")
      (footprint "eagle-import:C0805")
      (libsource (lib "eagle-import") (part "C-EUC0805"))
    )
    (comp (ref "C224")
      (value "1n")
      (footprint "eagle-import:C0603")
      (libsource (lib "eagle-import") (part "C-EUC0603"))
    )
    (comp (ref "C228")
      (value "1n")
      (footprint "eagle-import:C0603")
      (libsource (lib "eagle-import") (part "C-EUC0603"))
    )
    (comp (ref "C403")
      (value "47u/16V")
      (footprint "eagle-import:C1210")
      (libsource (lib "eagle-import") (part "C-EUC1210"))
    )
    (comp (ref "C404")
      (value "100n")
      (footprint "eagle-import:C0603")
      (libsource (lib "eagle-import") (part "C-EUC0603"))
    )
    (comp (ref "C405")
      (value "2u2")
      (footprint "eagle-import:C0603")
      (libsource (lib "eagle-import") (part "C-EUC0603"))
    )
    (comp (ref "C406")
      (value "1uF")
      (footprint "eagle-import:C0603")
      (libsource (lib "eagle-import") (part "C-EUC0603"))
    )
    (comp (ref "C407")
      (value "100p")
      (footprint "eagle-import:C0603")
      (libsource (lib "eagle-import") (part "C-EUC0603"))
    )
    (comp (ref "C409")
      (value "100p")
      (footprint "eagle-import:C0603")
      (libsource (lib "eagle-import") (part "C-EUC0603"))
    )
    (comp (ref "D403")
      (value "B240A")
      (footprint "eagle-import:DO214AC")
      (libsource (lib "eagle-import") (part "DIODE-DO214AC"))
    )
    (comp (ref "D404")
      (value "B240A")
      (footprint "eagle-import:DO214AC")
      (libsource (lib "eagle-import") (part "DIODE-DO214AC"))
    )
    (comp (ref "H1")
      (value "36103205")
      (footprint "eagle-import:WE-SHC_SMD-FRAME_36103205")
      (libsource (lib "eagle-import") (part "WE-SHC_SMD-FRAME_36103205"))
    )
    (comp (ref "L5")
      (value "744025100")
      (footprint "eagle-import:WE-TPC_2811_2813")
      (libsource (lib "eagle-import") (part "WE-TPC_2811/2813"))
    )
    (comp (ref "L6")
      (value "100nH")
      (footprint "eagle-import:WE-KI_0805")
      (libsource (lib "eagle-import") (part "WE-KI_0805_744760210A"))
    )
    (comp (ref "L7")
      (value "100nH")
      (footprint "eagle-import:WE-KI_0805")
      (libsource (lib "eagle-import") (part "WE-KI_0805_744760210A"))
    )
    (comp (ref "L9")
      (value "100nH")
      (footprint "eagle-import:WE-KI_0805")
      (libsource (lib "eagle-import") (part "WE-KI_0805_744760210A"))
    )
    (comp (ref "L209")
      (value "742863160")
      (footprint "eagle-import:R0603")
      (libsource (lib "eagle-import") (part "L-EUR0603"))
    )
    (comp (ref "L403")
      (value "744025100")
      (footprint "eagle-import:WE-TPC_2811_2813")
      (libsource (lib "eagle-import") (part "WE-TPC_2811/2813"))
    )
    (comp (ref "L404")
      (value "744025100")
      (footprint "eagle-import:WE-TPC_2811_2813")
      (libsource (lib "eagle-import") (part "WE-TPC_2811/2813"))
    )
    (comp (ref "L405")
      (value "744025100")
      (footprint "eagle-import:WE-TPC_2811_2813")
      (libsource (lib "eagle-import") (part "WE-TPC_2811/2813"))
    )
    (comp (ref "N5")
      (value "TLV170IDBV")
      (footprint "eagle-import:SOT-23L")
      (libsource (lib "eagle-import") (part "OPV_1SOT23-3"))
    )
    (comp (ref "N401")
      (value "LT3471EDD")
      (footprint "eagle-import:DFN_10POL_3X3MM+0,2MM")
      (fields (field (name "SPICEPREFIX") "X"))
      (libsource (lib "eagle-import") (part "LT3471"))
    )
    (comp (ref "R24")
      (value "0")
      (footprint "eagle-import:R0603")
      (libsource (lib "eagle-import") (part "R-EU_R0603"))
    )
    (comp (ref "R31")
      (value "0")
      (footprint "eagle-import:R0603")
      (libsource (lib "eagle-import") (part "R-EU_R0603"))
    )
    (comp (ref "R208")
      (value "1k")
      (footprint "eagle-import:R0603")
      (libsource (lib "eagle-import") (part "R-EU_R0603"))
    )
    (comp (ref "R209")
      (value "4k7")
      (footprint "eagle-import:R0603")
      (libsource (lib "eagle-import") (part "R-EU_R0603"))
    )
    (comp (ref "R210")
      (value "100k")
      (footprint "eagle-import:R0603")
      (libsource (lib "eagle-import") (part "R-EU_R0603"))
    )
    (comp (ref "R212")
      (value "68k")
      (footprint "eagle-import:R0603")
      (libsource (lib "eagle-import") (part "R-EU_R0603"))
    )
    (comp (ref "R402")
      (value "10k")
      (footprint "eagle-import:R0603")
      (libsource (lib "eagle-import") (part "R-EU_R0603"))
    )
    (comp (ref "R404")
      (value "22k")
      (footprint "eagle-import:R0603")
      (libsource (lib "eagle-import") (part "R-EU_R0603"))
    )
    (comp (ref "R405")
      (value "10k")
      (footprint "eagle-import:R0603")
      (libsource (lib "eagle-import") (part "R-EU_R0603"))
    )
    (comp (ref "R406")
      (value "51k")
      (footprint "eagle-import:R0603")
      (libsource (lib "eagle-import") (part "R-EU_R0603"))
    )
    (comp (ref "R407")
      (value "160k")
      (footprint "eagle-import:R0603")
      (libsource (lib "eagle-import") (part "R-EU_R0603"))
    )
    (comp (ref "R408")
      (value "39k")
      (footprint "eagle-import:R0603")
      (libsource (lib "eagle-import") (part "R-EU_R0603"))
    )
    (comp (ref "S401")
      (value "1301.9320")
      (footprint "eagle-import:1301.93XX")
      (libsource (lib "eagle-import") (part "1301.93XX"))
    )
    (comp (ref "C52")
      (value "875015119003")
      (footprint "eagle-import:WE_WCAP-PHGP")
      (libsource (lib "eagle-import") (part "KONDENSATOR_WE_WCAP_PHET_7,3X4,3X1,9MM"))
    )
    (comp (ref "C53")
      (value "875015119003")
      (footprint "eagle-import:WE_WCAP-PHGP")
      (libsource (lib "eagle-import") (part "KONDENSATOR_WE_WCAP_PHET_7,3X4,3X1,9MM"))
    )
    (comp (ref "C54")
      (value "100n")
      (footprint "eagle-import:C0603")
      (libsource (lib "eagle-import") (part "C-EUC0603"))
    )
    (comp (ref "C55")
      (value "100n")
      (footprint "eagle-import:C0603")
      (libsource (lib "eagle-import") (part "C-EUC0603"))
    )
    (comp (ref "C56")
      (value "100n")
      (footprint "eagle-import:C0603")
      (libsource (lib "eagle-import") (part "C-EUC0603"))
    )
    (comp (ref "C57")
      (value "1u")
      (footprint "eagle-import:C0603")
      (libsource (lib "eagle-import") (part "C-EUC0603"))
    )
    (comp (ref "C59")
      (value "1u")
      (footprint "eagle-import:C0603")
      (libsource (lib "eagle-import") (part "C-EUC0603"))
    )
    (comp (ref "C60")
      (value "100n")
      (footprint "eagle-import:C0603")
      (libsource (lib "eagle-import") (part "C-EUC0603"))
    )
    (comp (ref "C61")
      (value "1u")
      (footprint "eagle-import:C0603")
      (libsource (lib "eagle-import") (part "C-EUC0603"))
    )
    (comp (ref "C101")
      (value "100n")
      (footprint "eagle-import:C0603")
      (libsource (lib "eagle-import") (part "C-EUC0603"))
    )
    (comp (ref "C102")
      (value "4u7")
      (footprint "eagle-import:C0603")
      (libsource (lib "eagle-import") (part "C-EUC0603"))
    )
    (comp (ref "C103")
      (value "100n")
      (footprint "eagle-import:C0603")
      (libsource (lib "eagle-import") (part "C-EUC0603"))
    )
    (comp (ref "C104")
      (value "100n")
      (footprint "eagle-import:C0603")
      (libsource (lib "eagle-import") (part "C-EUC0603"))
    )
    (comp (ref "C105")
      (value "100n")
      (footprint "eagle-import:C0603")
      (libsource (lib "eagle-import") (part "C-EUC0603"))
    )
    (comp (ref "C106")
      (value "100n")
      (footprint "eagle-import:C0603")
      (libsource (lib "eagle-import") (part "C-EUC0603"))
    )
    (comp (ref "C107")
      (value "100n")
      (footprint "eagle-import:C0603")
      (libsource (lib "eagle-import") (part "C-EUC0603"))
    )
    (comp (ref "C108")
      (value "100n")
      (footprint "eagle-import:C0603")
      (libsource (lib "eagle-import") (part "C-EUC0603"))
    )
    (comp (ref "C413")
      (value "1u")
      (footprint "eagle-import:C0603")
      (libsource (lib "eagle-import") (part "C-EUC0603"))
    )
    (comp (ref "C418")
      (value "10n")
      (footprint "eagle-import:C0603")
      (libsource (lib "eagle-import") (part "C-EUC0603"))
    )
    (comp (ref "C419")
      (value "2u2")
      (footprint "eagle-import:C0603")
      (libsource (lib "eagle-import") (part "C-EUC0603"))
    )
    (comp (ref "D5")
      (value "PESD5V0X1BL,315")
      (footprint "eagle-import:DIODFN100X60X60-2")
      (libsource (lib "eagle-import") (part "PESD5V0X1BL,315"))
    )
    (comp (ref "D6")
      (value "PESD5V0X1BL,315")
      (footprint "eagle-import:DIODFN100X60X60-2")
      (libsource (lib "eagle-import") (part "PESD5V0X1BL,315"))
    )
    (comp (ref "D7")
      (value "PESD5V0X1BL,315")
      (footprint "eagle-import:DIODFN100X60X60-2")
      (libsource (lib "eagle-import") (part "PESD5V0X1BL,315"))
    )
    (comp (ref "JP3")
      (value "n.b.")
      (footprint "eagle-import:1X04")
      (libsource (lib "eagle-import") (part "PINHD-1X4"))
    )
    (comp (ref "L8")
      (value "100nH")
      (footprint "eagle-import:WE-KI_0805")
      (libsource (lib "eagle-import") (part "WE-KI_0805_744760210A"))
    )
    (comp (ref "M1")
      (value "BM83SM1")
      (footprint "eagle-import:BM83")
      (libsource (lib "eagle-import") (part "BM83"))
    )
    (comp (ref "N101")
      (value "LSM6DSL")
      (footprint "eagle-import:LGA-14")
      (libsource (lib "eagle-import") (part "LSM6DSLTR"))
    )
    (comp (ref "N404")
      (value "TPS79933DDCR")
      (footprint "eagle-import:SOT-23-5")
      (libsource (lib "eagle-import") (part "TPS79933"))
    )
    (comp (ref "R101")
      (value "10k")
      (footprint "eagle-import:R0603")
      (libsource (lib "eagle-import") (part "R-EU_R0603"))
    )
    (comp (ref "U101")
      (value "ATXMEGA64A3-MH")
      (footprint "eagle-import:MLF-(VQFN)-64M2-64")
      (libsource (lib "eagle-import") (part "ATXMEGA64A3-MH"))
    )
    (comp (ref "X7")
      (value "n.b.")
      (footprint "eagle-import:LöTBRüCKE_2")
      (libsource (lib "eagle-import") (part "LB1_2"))
    )
    (comp (ref "X102")
      (value "n.b.")
      (footprint "eagle-import:AVRPDI4")
      (libsource (lib "eagle-import") (part "AVRPDI"))
    )
  )
  (nets
    (net (code "1") (name "+4.1V") (class "Default")
      (node (ref "C305") (pin "1") (pinfunction "1_1") (pintype "passive"))
      (node (ref "D302") (pin "2") (pinfunction "2_2") (pintype "passive"))
      (node (ref "N301") (pin "10") (pinfunction "OUT_10") (pintype "power_in"))
      (node (ref "R305") (pin "2") (pinfunction "2_2") (pintype "passive"))
      (node (ref "R314") (pin "2") (pinfunction "2_2") (pintype "passive"))
      (node (ref "R315") (pin "2") (pinfunction "2_2") (pintype "passive"))
      (node (ref "R317") (pin "2") (pinfunction "2_2") (pintype "passive"))
      (node (ref "TP302") (pin "TP") (pinfunction "TP_TP") (pintype "input"))
      (node (ref "V301") (pin "2") (pinfunction "S_2") (pintype "passive"))
      (node (ref "V303") (pin "2") (pinfunction "S_2") (pintype "passive"))
    )
    (net (code "2") (name "+4V5") (class "Default")
      (node (ref "C307") (pin "2") (pinfunction "2_2") (pintype "passive"))
      (node (ref "C413") (pin "1") (pinfunction "1_1") (pintype "passive"))
      (node (ref "C50") (pin "2+") (pinfunction "+_2+") (pintype "passive"))
      (node (ref "D1") (pin "2") (pinfunction "+_2") (pintype "passive"))
      (node (ref "D2") (pin "2") (pinfunction "+_2") (pintype "passive"))
      (node (ref "H401") (pin "A") (pinfunction "A_A") (pintype "passive"))
      (node (ref "L7") (pin "1") (pinfunction "1_1") (pintype "passive"))
      (node (ref "N302") (pin "1") (pinfunction "VOUT_1") (pintype "bidirectional"))
      (node (ref "N302") (pin "12") (pinfunction "FB_12") (pintype "bidirectional"))
      (node (ref "N404") (pin "1") (pinfunction "IN_1") (pintype "power_in"))
      (node (ref "N404") (pin "3") (pinfunction "EN_3") (pintype "input"))
      (node (ref "TP303") (pin "TP") (pinfunction "TP_TP") (pintype "input"))
    )
    (net (code "3") (name "+5V") (class "Default")
      (node (ref "C15") (pin "2") (pinfunction "2_2") (pintype "passive"))
      (node (ref "C17") (pin "2") (pinfunction "2_2") (pintype "passive"))
      (node (ref "C19") (pin "2") (pinfunction "2_2") (pintype "passive"))
      (node (ref "C202") (pin "2") (pinfunction "2_2") (pintype "passive"))
      (node (ref "C203") (pin "1") (pinfunction "1_1") (pintype "passive"))
      (node (ref "C21") (pin "2") (pinfunction "2_2") (pintype "passive"))
      (node (ref "C210") (pin "2") (pinfunction "2_2") (pintype "passive"))
      (node (ref "C216") (pin "2") (pinfunction "2_2") (pintype "passive"))
      (node (ref "C23") (pin "2") (pinfunction "2_2") (pintype "passive"))
      (node (ref "C37") (pin "2+") (pinfunction "+_2+") (pintype "passive"))
      (node (ref "C43") (pin "1") (pinfunction "1_1") (pintype "passive"))
      (node (ref "C44") (pin "1") (pinfunction "1_1") (pintype "passive"))
      (node (ref "IC1") (pin "4") (pinfunction "VCC_4") (pintype "power_in"))
      (node (ref "IC2") (pin "4") (pinfunction "VCC_4") (pintype "power_in"))
      (node (ref "IC201") (pin "4") (pinfunction "VCC_4") (pintype "power_in"))
      (node (ref "IC3") (pin "4") (pinfunction "VCC_4") (pintype "power_in"))
      (node (ref "IC4") (pin "4") (pinfunction "VCC_4") (pintype "power_in"))
      (node (ref "L201") (pin "2") (pinfunction "2_2") (pintype "passive"))
      (node (ref "L6") (pin "2") (pinfunction "2_2") (pintype "passive"))
      (node (ref "N1") (pin "8") (pinfunction "VCC_8") (pintype "power_in"))
      (node (ref "N2") (pin "8") (pinfunction "VCC_8") (pintype "power_in"))
      (node (ref "N5") (pin "5") (pinfunction "VCC_5") (pintype "power_in"))
      (node (ref "N6") (pin "7") (pinfunction "VCC_7") (pintype "power_in"))
      (node (ref "N7") (pin "7") (pinfunction "VCC_7") (pintype "power_in"))
    )
    (net (code "4") (name "-5V") (class "Default")
      (node (ref "C16") (pin "1") (pinfunction "1_1") (pintype "passive"))
      (node (ref "C18") (pin "1") (pinfunction "1_1") (pintype "passive"))
      (node (ref "C20") (pin "1") (pinfunction "1_1") (pintype "passive"))
      (node (ref "C204") (pin "1") (pinfunction "1_1") (pintype "passive"))
      (node (ref "C209") (pin "1") (pinfunction "1_1") (pintype "passive"))
      (node (ref "C211") (pin "1") (pinfunction "1_1") (pintype "passive"))
      (node (ref "C217") (pin "1") (pinfunction "1_1") (pintype "passive"))
      (node (ref "C22") (pin "1") (pinfunction "1_1") (pintype "passive"))
      (node (ref "C24") (pin "1") (pinfunction "1_1") (pintype "passive"))
      (node (ref "C38") (pin "1-") (pinfunction "-_1-") (pintype "passive"))
      (node (ref "C45") (pin "2") (pinfunction "2_2") (pintype "passive"))
      (node (ref "C46") (pin "2") (pinfunction "2_2") (pintype "passive"))
      (node (ref "IC1") (pin "7") (pinfunction "VSS_7") (pintype "power_in"))
      (node (ref "IC2") (pin "7") (pinfunction "VSS_7") (pintype "power_in"))
      (node (ref "IC201") (pin "7") (pinfunction "VSS_7") (pintype "power_in"))
      (node (ref "IC3") (pin "7") (pinfunction "VSS_7") (pintype "power_in"))
      (node (ref "IC4") (pin "7") (pinfunction "VSS_7") (pintype "power_in"))
      (node (ref "L203") (pin "2") (pinfunction "2_2") (pintype "passive"))
      (node (ref "L9") (pin "2") (pinfunction "2_2") (pintype "passive"))
      (node (ref "N1") (pin "4") (pinfunction "VSS_4") (pintype "power_in"))
      (node (ref "N2") (pin "4") (pinfunction "VSS_4") (pintype "power_in"))
      (node (ref "N6") (pin "4") (pinfunction "VSS_4") (pintype "power_in"))
      (node (ref "N7") (pin "4") (pinfunction "VSS_4") (pintype "power_in"))
    )
    (net (code "5") (name "1A") (class "Default")
      (node (ref "R3") (pin "12") (pinfunction "2_12") (pintype "passive"))
      (node (ref "U101") (pin "37") (pinfunction "PE1_37") (pintype "bidirectional"))
    )
    (net (code "6") (name "1B") (class "Default")
      (node (ref "R3") (pin "10") (pinfunction "2_10") (pintype "passive"))
      (node (ref "U101") (pin "38") (pinfunction "PE2_38") (pintype "bidirectional"))
    )
    (net (code "7") (name "1C") (class "Default")
      (node (ref "R3") (pin "8") (pinfunction "2_8") (pintype "passive"))
      (node (ref "U101") (pin "39") (pinfunction "PE3_39") (pintype "bidirectional"))
    )
    (net (code "8") (name "1D") (class "Default")
      (node (ref "R3") (pin "6") (pinfunction "2_6") (pintype "passive"))
      (node (ref "U101") (pin "40") (pinfunction "PE4_40") (pintype "bidirectional"))
    )
    (net (code "9") (name "1E") (class "Default")
      (node (ref "R3") (pin "4") (pinfunction "2_4") (pintype "passive"))
      (node (ref "U101") (pin "41") (pinfunction "PE5_41") (pintype "bidirectional"))
    )
    (net (code "10") (name "1F") (class "Default")
      (node (ref "R3") (pin "2") (pinfunction "2_2") (pintype "passive"))
      (node (ref "U101") (pin "42") (pinfunction "PE6_42") (pintype "bidirectional"))
    )
    (net (code "11") (name "1G") (class "Default")
      (node (ref "R2") (pin "16") (pinfunction "2_16") (pintype "passive"))
      (node (ref "U101") (pin "43") (pinfunction "PE7_43") (pintype "bidirectional"))
    )
    (net (code "12") (name "2A") (class "Default")
      (node (ref "R2") (pin "12") (pinfunction "2_12") (pintype "passive"))
      (node (ref "U101") (pin "47") (pinfunction "PF1_47") (pintype "bidirectional"))
    )
    (net (code "13") (name "2B") (class "Default")
      (node (ref "R2") (pin "10") (pinfunction "2_10") (pintype "passive"))
      (node (ref "U101") (pin "48") (pinfunction "PF2_48") (pintype "bidirectional"))
    )
    (net (code "14") (name "2C") (class "Default")
      (node (ref "R2") (pin "8") (pinfunction "2_8") (pintype "passive"))
      (node (ref "U101") (pin "49") (pinfunction "PF3_49") (pintype "bidirectional"))
    )
    (net (code "15") (name "2D") (class "Default")
      (node (ref "R2") (pin "6") (pinfunction "2_6") (pintype "passive"))
      (node (ref "U101") (pin "50") (pinfunction "PF4_50") (pintype "bidirectional"))
    )
    (net (code "16") (name "2E") (class "Default")
      (node (ref "R2") (pin "4") (pinfunction "2_4") (pintype "passive"))
      (node (ref "U101") (pin "51") (pinfunction "PF5_51") (pintype "bidirectional"))
    )
    (net (code "17") (name "2F") (class "Default")
      (node (ref "R2") (pin "2") (pinfunction "2_2") (pintype "passive"))
      (node (ref "U101") (pin "54") (pinfunction "PF6_54") (pintype "bidirectional"))
    )
    (net (code "18") (name "2G") (class "Default")
      (node (ref "R1") (pin "16") (pinfunction "2_16") (pintype "passive"))
      (node (ref "U101") (pin "55") (pinfunction "PF7_55") (pintype "bidirectional"))
    )
    (net (code "19") (name "ADAP_IN") (class "Default")
      (node (ref "C55") (pin "2") (pinfunction "2_2") (pintype "passive"))
      (node (ref "C59") (pin "2") (pinfunction "2_2") (pintype "passive"))
      (node (ref "D7") (pin "1") (pinfunction "P$1_1") (pintype "bidirectional"))
      (node (ref "JP3") (pin "1") (pinfunction "1_1") (pintype "passive"))
      (node (ref "M1") (pin "22") (pinfunction "ADAP_IN_22") (pintype "power_in"))
    )
    (net (code "20") (name "ADC3") (class "Default")
      (node (ref "C228") (pin "1") (pinfunction "1_1") (pintype "passive"))
      (node (ref "L209") (pin "2") (pinfunction "2_2") (pintype "passive"))
      (node (ref "U101") (pin "1") (pinfunction "PA3_1") (pintype "bidirectional"))
    )
    (net (code "21") (name "ADC7") (class "Default")
      (node (ref "R320") (pin "1") (pinfunction "1_1") (pintype "passive"))
      (node (ref "R322") (pin "2") (pinfunction "2_2") (pintype "passive"))
      (node (ref "TP304") (pin "TP") (pinfunction "TP_TP") (pintype "input"))
      (node (ref "U101") (pin "5") (pinfunction "PA7_5") (pintype "bidirectional"))
    )
    (net (code "22") (name "AGND") (class "Default")
      (node (ref "C1") (pin "2") (pinfunction "2_2") (pintype "passive"))
      (node (ref "C10") (pin "2") (pinfunction "2_2") (pintype "passive"))
      (node (ref "C13") (pin "1") (pinfunction "1_1") (pintype "passive"))
      (node (ref "C15") (pin "1") (pinfunction "1_1") (pintype "passive"))
      (node (ref "C16") (pin "2") (pinfunction "2_2") (pintype "passive"))
      (node (ref "C17") (pin "1") (pinfunction "1_1") (pintype "passive"))
      (node (ref "C18") (pin "2") (pinfunction "2_2") (pintype "passive"))
      (node (ref "C19") (pin "1") (pinfunction "1_1") (pintype "passive"))
      (node (ref "C20") (pin "2") (pinfunction "2_2") (pintype "passive"))
      (node (ref "C201") (pin "2") (pinfunction "2_2") (pintype "passive"))
      (node (ref "C202") (pin "1") (pinfunction "1_1") (pintype "passive"))
      (node (ref "C203") (pin "2") (pinfunction "2_2") (pintype "passive"))
      (node (ref "C204") (pin "2") (pinfunction "2_2") (pintype "passive"))
      (node (ref "C205") (pin "2") (pinfunction "2_2") (pintype "passive"))
      (node (ref "C206") (pin "2") (pinfunction "2_2") (pintype "passive"))
      (node (ref "C208") (pin "2") (pinfunction "2_2") (pintype "passive"))
      (node (ref "C209") (pin "2") (pinfunction "2_2") (pintype "passive"))
      (node (ref "C21") (pin "1") (pinfunction "1_1") (pintype "passive"))
      (node (ref "C210") (pin "1") (pinfunction "1_1") (pintype "passive"))
      (node (ref "C211") (pin "2") (pinfunction "2_2") (pintype "passive"))
      (node (ref "C212") (pin "2") (pinfunction "2_2") (pintype "passive"))
      (node (ref "C214") (pin "2") (pinfunction "2_2") (pintype "passive"))
      (node (ref "C215") (pin "2") (pinfunction "2_2") (pintype "passive"))
      (node (ref "C216") (pin "1") (pinfunction "1_1") (pintype "passive"))
      (node (ref "C217") (pin "2") (pinfunction "2_2") (pintype "passive"))
      (node (ref "C22") (pin "2") (pinfunction "2_2") (pintype "passive"))
      (node (ref "C220") (pin "1") (pinfunction "1_1") (pintype "passive"))
      (node (ref "C224") (pin "2") (pinfunction "2_2") (pintype "passive"))
      (node (ref "C23") (pin "1") (pinfunction "1_1") (pintype "passive"))
      (node (ref "C24") (pin "2") (pinfunction "2_2") (pintype "passive"))
      (node (ref "C26") (pin "2") (pinfunction "2_2") (pintype "passive"))
      (node (ref "C28") (pin "1") (pinfunction "1_1") (pintype "passive"))
      (node (ref "C30") (pin "2") (pinfunction "2_2") (pintype "passive"))
      (node (ref "C31") (pin "1") (pinfunction "1_1") (pintype "passive"))
      (node (ref "C33") (pin "1") (pinfunction "1_1") (pintype "passive"))
      (node (ref "C35") (pin "2") (pinfunction "2_2") (pintype "passive"))
      (node (ref "C36") (pin "1") (pinfunction "1_1") (pintype "passive"))
      (node (ref "C37") (pin "1-") (pinfunction "-_1-") (pintype "passive"))
      (node (ref "C38") (pin "2+") (pinfunction "+_2+") (pintype "passive"))
      (node (ref "C39") (pin "2") (pinfunction "2_2") (pintype "passive"))
      (node (ref "C403") (pin "2") (pinfunction "2_2") (pintype "passive"))
      (node (ref "C404") (pin "2") (pinfunction "2_2") (pintype "passive"))
      (node (ref "C406") (pin "2") (pinfunction "2_2") (pintype "passive"))
      (node (ref "C43") (pin "2") (pinfunction "2_2") (pintype "passive"))
      (node (ref "C44") (pin "2") (pinfunction "2_2") (pintype "passive"))
      (node (ref "C45") (pin "1") (pinfunction "1_1") (pintype "passive"))
      (node (ref "C46") (pin "1") (pinfunction "1_1") (pintype "passive"))
      (node (ref "C48") (pin "2") (pinfunction "2_2") (pintype "passive"))
      (node (ref "C49") (pin "1") (pinfunction "1_1") (pintype "passive"))
      (node (ref "C51") (pin "1-") (pinfunction "-_1-") (pintype "passive"))
      (node (ref "D403") (pin "C") (pinfunction "C_C") (pintype "passive"))
      (node (ref "H1") (pin "1") (pinfunction "GND_1") (pintype "power_in"))
      (node (ref "H1") (pin "10") (pinfunction "GND_10") (pintype "power_in"))
      (node (ref "H1") (pin "11") (pinfunction "GND_11") (pintype "power_in"))
      (node (ref "H1") (pin "12") (pinfunction "GND_12") (pintype "power_in"))
      (node (ref "H1") (pin "13") (pinfunction "GND_13") (pintype "power_in"))
      (node (ref "H1") (pin "14") (pinfunction "GND_14") (pintype "power_in"))
      (node (ref "H1") (pin "15") (pinfunction "GND_15") (pintype "power_in"))
      (node (ref "H1") (pin "16") (pinfunction "GND_16") (pintype "power_in"))
      (node (ref "H1") (pin "2") (pinfunction "GND_2") (pintype "power_in"))
      (node (ref "H1") (pin "3") (pinfunction "GND_3") (pintype "power_in"))
      (node (ref "H1") (pin "4") (pinfunction "GND_4") (pintype "power_in"))
      (node (ref "H1") (pin "5") (pinfunction "GND_5") (pintype "power_in"))
      (node (ref "H1") (pin "6") (pinfunction "GND_6") (pintype "power_in"))
      (node (ref "H1") (pin "7") (pinfunction "GND_7") (pintype "power_in"))
      (node (ref "H1") (pin "8") (pinfunction "GND_8") (pintype "power_in"))
      (node (ref "H1") (pin "9") (pinfunction "GND_9") (pintype "power_in"))
      (node (ref "IC1") (pin "3") (pinfunction "GND_3") (pintype "power_in"))
      (node (ref "IC2") (pin "3") (pinfunction "GND_3") (pintype "power_in"))
      (node (ref "IC201") (pin "3") (pinfunction "GND_3") (pintype "power_in"))
      (node (ref "IC3") (pin "3") (pinfunction "GND_3") (pintype "power_in"))
      (node (ref "IC4") (pin "3") (pinfunction "GND_3") (pintype "power_in"))
      (node (ref "L204") (pin "2") (pinfunction "2_2") (pintype "passive"))
      (node (ref "L5") (pin "1") (pinfunction "1_1") (pintype "passive"))
      (node (ref "N401") (pin "11") (pinfunction "GND_11") (pintype "bidirectional"))
      (node (ref "N401") (pin "5") (pinfunction "FB2N_5") (pintype "bidirectional"))
      (node (ref "N5") (pin "2") (pinfunction "VSS_2") (pintype "power_in"))
      (node (ref "N7") (pin "3") (pinfunction "IN+_3") (pintype "input"))
      (node (ref "R10") (pin "2") (pinfunction "2_2") (pintype "passive"))
      (node (ref "R14") (pin "1") (pinfunction "1_1") (pintype "passive"))
      (node (ref "R16") (pin "1") (pinfunction "1_1") (pintype "passive"))
      (node (ref "R17") (pin "1") (pinfunction "1_1") (pintype "passive"))
      (node (ref "R203") (pin "2") (pinfunction "2_2") (pintype "passive"))
      (node (ref "R212") (pin "1") (pinfunction "1_1") (pintype "passive"))
      (node (ref "R30") (pin "1") (pinfunction "1_1") (pintype "passive"))
      (node (ref "R31") (pin "1") (pinfunction "1_1") (pintype "passive"))
      (node (ref "R408") (pin "1") (pinfunction "1_1") (pintype "passive"))
      (node (ref "R6") (pin "1") (pinfunction "1_1") (pintype "passive"))
      (node (ref "R7") (pin "2") (pinfunction "2_2") (pintype "passive"))
      (node (ref "R8") (pin "2") (pinfunction "2_2") (pintype "passive"))
      (node (ref "R9") (pin "2") (pinfunction "2_2") (pintype "passive"))
      (node (ref "TP5") (pin "TP") (pinfunction "TP_TP") (pintype "input"))
      (node (ref "V1") (pin "2") (pinfunction "S_2") (pintype "passive"))
    )
    (net (code "23") (name "AIL") (class "Default")
      (node (ref "C66") (pin "1") (pinfunction "1_1") (pintype "passive"))
      (node (ref "M1") (pin "12") (pinfunction "AIL_12") (pintype "input"))
    )
    (net (code "24") (name "AIR") (class "Default")
      (node (ref "C65") (pin "1") (pinfunction "1_1") (pintype "passive"))
      (node (ref "M1") (pin "11") (pinfunction "AIR_11") (pintype "input"))
    )
    (net (code "25") (name "B0") (class "Default")
      (node (ref "R1") (pin "10") (pinfunction "2_10") (pintype "passive"))
      (node (ref "U101") (pin "62") (pinfunction "PA0_62") (pintype "bidirectional"))
    )
    (net (code "26") (name "B1") (class "Default")
      (node (ref "R1") (pin "8") (pinfunction "2_8") (pintype "passive"))
      (node (ref "U101") (pin "63") (pinfunction "PA1_63") (pintype "bidirectional"))
    )
    (net (code "27") (name "B2") (class "Default")
      (node (ref "R1") (pin "6") (pinfunction "2_6") (pintype "passive"))
      (node (ref "U101") (pin "64") (pinfunction "PA2_64") (pintype "bidirectional"))
    )
    (net (code "28") (name "B3") (class "Default")
      (node (ref "R1") (pin "4") (pinfunction "2_4") (pintype "passive"))
      (node (ref "U101") (pin "2") (pinfunction "PA4_2") (pintype "bidirectional"))
    )
    (net (code "29") (name "B4") (class "Default")
      (node (ref "R1") (pin "2") (pinfunction "2_2") (pintype "passive"))
      (node (ref "U101") (pin "3") (pinfunction "PA5_3") (pintype "bidirectional"))
    )
    (net (code "30") (name "CLK_PC1") (class "Default")
      (node (ref "N101") (pin "13") (pinfunction "SCL_13") (pintype "input"))
      (node (ref "U101") (pin "17") (pinfunction "PC1_17") (pintype "bidirectional"))
    )
    (net (code "31") (name "COM") (class "Default")
      (node (ref "R2") (pin "14") (pinfunction "2_14") (pintype "passive"))
      (node (ref "U101") (pin "46") (pinfunction "PF0_46") (pintype "bidirectional"))
    )
    (net (code "32") (name "DM") (class "Default")
      (node (ref "D5") (pin "1") (pinfunction "P$1_1") (pintype "bidirectional"))
      (node (ref "JP3") (pin "2") (pinfunction "2_2") (pintype "passive"))
      (node (ref "M1") (pin "36") (pinfunction "DM_36") (pintype "bidirectional"))
    )
    (net (code "33") (name "DP") (class "Default")
      (node (ref "D6") (pin "1") (pinfunction "P$1_1") (pintype "bidirectional"))
      (node (ref "JP3") (pin "3") (pinfunction "3_3") (pintype "passive"))
      (node (ref "M1") (pin "37") (pinfunction "DP_37") (pintype "bidirectional"))
    )
    (net (code "34") (name "GND") (class "Default")
      (node (ref "C101") (pin "2") (pinfunction "2_2") (pintype "passive"))
      (node (ref "C102") (pin "2") (pinfunction "2_2") (pintype "passive"))
      (node (ref "C103") (pin "2") (pinfunction "2_2") (pintype "passive"))
      (node (ref "C104") (pin "2") (pinfunction "2_2") (pintype "passive"))
      (node (ref "C105") (pin "2") (pinfunction "2_2") (pintype "passive"))
      (node (ref "C106") (pin "2") (pinfunction "2_2") (pintype "passive"))
      (node (ref "C107") (pin "2") (pinfunction "2_2") (pintype "passive"))
      (node (ref "C108") (pin "2") (pinfunction "2_2") (pintype "passive"))
      (node (ref "C2") (pin "2") (pinfunction "2_2") (pintype "passive"))
      (node (ref "C218") (pin "2") (pinfunction "2_2") (pintype "passive"))
      (node (ref "C228") (pin "2") (pinfunction "2_2") (pintype "passive"))
      (node (ref "C25") (pin "2") (pinfunction "2_2") (pintype "passive"))
      (node (ref "C29") (pin "2") (pinfunction "2_2") (pintype "passive"))
      (node (ref "C3") (pin "2") (pinfunction "2_2") (pintype "passive"))
      (node (ref "C3") (pin "4") (pinfunction "2_4") (pintype "passive"))
      (node (ref "C3") (pin "6") (pinfunction "2_6") (pintype "passive"))
      (node (ref "C3") (pin "8") (pinfunction "2_8") (pintype "passive"))
      (node (ref "C301") (pin "2") (pinfunction "2_2") (pintype "passive"))
      (node (ref "C302") (pin "2") (pinfunction "2_2") (pintype "passive"))
      (node (ref "C303") (pin "1") (pinfunction "1_1") (pintype "passive"))
      (node (ref "C304") (pin "2") (pinfunction "2_2") (pintype "bidirectional"))
      (node (ref "C305") (pin "2") (pinfunction "2_2") (pintype "passive"))
      (node (ref "C307") (pin "1") (pinfunction "1_1") (pintype "passive"))
      (node (ref "C4") (pin "2") (pinfunction "2_2") (pintype "passive"))
      (node (ref "C4") (pin "4") (pinfunction "2_4") (pintype "passive"))
      (node (ref "C4") (pin "6") (pinfunction "2_6") (pintype "passive"))
      (node (ref "C4") (pin "8") (pinfunction "2_8") (pintype "passive"))
      (node (ref "C413") (pin "2") (pinfunction "2_2") (pintype "passive"))
      (node (ref "C418") (pin "2") (pinfunction "2_2") (pintype "passive"))
      (node (ref "C419") (pin "2") (pinfunction "2_2") (pintype "passive"))
      (node (ref "C5") (pin "2") (pinfunction "2_2") (pintype "passive"))
      (node (ref "C5") (pin "4") (pinfunction "2_4") (pintype "passive"))
      (node (ref "C5") (pin "6") (pinfunction "2_6") (pintype "passive"))
      (node (ref "C5") (pin "8") (pinfunction "2_8") (pintype "passive"))
      (node (ref "C50") (pin "1-") (pinfunction "-_1-") (pintype "passive"))
      (node (ref "C52") (pin "1-") (pinfunction "-_1-") (pintype "passive"))
      (node (ref "C53") (pin "1-") (pinfunction "-_1-") (pintype "passive"))
      (node (ref "C54") (pin "1") (pinfunction "1_1") (pintype "passive"))
      (node (ref "C55") (pin "1") (pinfunction "1_1") (pintype "passive"))
      (node (ref "C56") (pin "1") (pinfunction "1_1") (pintype "passive"))
      (node (ref "C57") (pin "1") (pinfunction "1_1") (pintype "passive"))
      (node (ref "C59") (pin "1") (pinfunction "1_1") (pintype "passive"))
      (node (ref "C6") (pin "1") (pinfunction "1_1") (pintype "passive"))
      (node (ref "C6") (pin "3") (pinfunction "1_3") (pintype "passive"))
      (node (ref "C6") (pin "5") (pinfunction "1_5") (pintype "passive"))
      (node (ref "C6") (pin "7") (pinfunction "1_7") (pintype "passive"))
      (node (ref "C60") (pin "1") (pinfunction "1_1") (pintype "passive"))
      (node (ref "C61") (pin "1") (pinfunction "1_1") (pintype "passive"))
      (node (ref "C63") (pin "2") (pinfunction "2_2") (pintype "passive"))
      (node (ref "C64") (pin "1") (pinfunction "1_1") (pintype "passive"))
      (node (ref "C68") (pin "2") (pinfunction "2_2") (pintype "passive"))
      (node (ref "C69") (pin "1") (pinfunction "1_1") (pintype "passive"))
      (node (ref "C7") (pin "1") (pinfunction "1_1") (pintype "passive"))
      (node (ref "C7") (pin "3") (pinfunction "1_3") (pintype "passive"))
      (node (ref "C7") (pin "5") (pinfunction "1_5") (pintype "passive"))
      (node (ref "C7") (pin "7") (pinfunction "1_7") (pintype "passive"))
      (node (ref "C8") (pin "1") (pinfunction "1_1") (pintype "passive"))
      (node (ref "C8") (pin "3") (pinfunction "1_3") (pintype "passive"))
      (node (ref "C8") (pin "5") (pinfunction "1_5") (pintype "passive"))
      (node (ref "C8") (pin "7") (pinfunction "1_7") (pintype "passive"))
      (node (ref "C9") (pin "2") (pinfunction "2_2") (pintype "passive"))
      (node (ref "D5") (pin "2") (pinfunction "P$2_2") (pintype "bidirectional"))
      (node (ref "D6") (pin "2") (pinfunction "P$2_2") (pintype "bidirectional"))
      (node (ref "D7") (pin "2") (pinfunction "P$2_2") (pintype "bidirectional"))
      (node (ref "D8") (pin "2") (pinfunction "P$2_2") (pintype "bidirectional"))
      (node (ref "JP3") (pin "4") (pinfunction "4_4") (pintype "passive"))
      (node (ref "M1") (pin "16") (pinfunction "GND_16") (pintype "power_in"))
      (node (ref "M1") (pin "50") (pinfunction "GND_50") (pintype "power_in"))
      (node (ref "M1") (pin "56") (pinfunction "GND_56") (pintype "power_in"))
      (node (ref "M1") (pin "57") (pinfunction "GND_57") (pintype "power_in"))
      (node (ref "N101") (pin "6") (pinfunction "GND_6") (pintype "power_in"))
      (node (ref "N101") (pin "7") (pinfunction "GND_7") (pintype "power_in"))
      (node (ref "N301") (pin "11") (pinfunction "GND_11") (pintype "power_in"))
      (node (ref "N301") (pin "3") (pinfunction "GND_3") (pintype "power_in"))
      (node (ref "N301") (pin "7") (pinfunction "ISET2_7") (pintype "input"))
      (node (ref "N301") (pin "P$1") (pinfunction "GND_P$1") (pintype "power_in"))
      (node (ref "N301") (pin "P$2") (pinfunction "GND_P$2") (pintype "power_in"))
      (node (ref "N301") (pin "P$3") (pinfunction "GND_P$3") (pintype "power_in"))
      (node (ref "N301") (pin "P$4") (pinfunction "GND_P$4") (pintype "power_in"))
      (node (ref "N301") (pin "P$5") (pinfunction "GND_P$5") (pintype "power_in"))
      (node (ref "N302") (pin "10") (pinfunction "SYNC_10") (pintype "bidirectional"))
      (node (ref "N302") (pin "11") (pinfunction "VSEL_11") (pintype "bidirectional"))
      (node (ref "N302") (pin "13") (pinfunction "GND_13") (pintype "bidirectional"))
      (node (ref "N302") (pin "3") (pinfunction "GND_3") (pintype "bidirectional"))
      (node (ref "N302") (pin "8") (pinfunction "GND_8") (pintype "bidirectional"))
      (node (ref "N302") (pin "9") (pinfunction "GND_9") (pintype "bidirectional"))
      (node (ref "N404") (pin "2") (pinfunction "GND_2") (pintype "power_in"))
      (node (ref "R21") (pin "1") (pinfunction "1_1") (pintype "passive"))
      (node (ref "R23") (pin "1") (pinfunction "1_1") (pintype "passive"))
      (node (ref "R24") (pin "2") (pinfunction "2_2") (pintype "passive"))
      (node (ref "R301") (pin "1") (pinfunction "1_1") (pintype "passive"))
      (node (ref "R303") (pin "1") (pinfunction "1_1") (pintype "passive"))
      (node (ref "R309") (pin "1") (pinfunction "1_1") (pintype "passive"))
      (node (ref "R31") (pin "2") (pinfunction "2_2") (pintype "passive"))
      (node (ref "R311") (pin "1") (pinfunction "1_1") (pintype "passive"))
      (node (ref "R312") (pin "P$1") (pinfunction "1_P$1") (pintype "passive"))
      (node (ref "R313") (pin "P$1") (pinfunction "1_P$1") (pintype "passive"))
      (node (ref "R319") (pin "1") (pinfunction "1_1") (pintype "passive"))
      (node (ref "R322") (pin "1") (pinfunction "1_1") (pintype "passive"))
      (node (ref "R45") (pin "1") (pinfunction "1_1") (pintype "passive"))
      (node (ref "R46") (pin "2") (pinfunction "2_2") (pintype "passive"))
      (node (ref "S301") (pin "P1") (pinfunction "1_P1") (pintype "bidirectional"))
      (node (ref "S301") (pin "P2") (pinfunction "1_P2") (pintype "bidirectional"))
      (node (ref "S401") (pin "P1") (pinfunction "1_P1") (pintype "bidirectional"))
      (node (ref "S401") (pin "P2") (pinfunction "1_P2") (pintype "bidirectional"))
      (node (ref "U101") (pin "14") (pinfunction "GND_14") (pintype "power_in"))
      (node (ref "U101") (pin "24") (pinfunction "GND_24") (pintype "power_in"))
      (node (ref "U101") (pin "34") (pinfunction "GND_34") (pintype "power_in"))
      (node (ref "U101") (pin "44") (pinfunction "GND_44") (pintype "power_in"))
      (node (ref "U101") (pin "52") (pinfunction "GND_52") (pintype "power_in"))
      (node (ref "U101") (pin "60") (pinfunction "GND_60") (pintype "power_in"))
      (node (ref "U101") (pin "TH") (pinfunction "GND_TH") (pintype "power_in"))
      (node (ref "U302") (pin "P$1") (pinfunction "P-_P$1") (pintype "bidirectional"))
      (node (ref "U302") (pin "P$2") (pinfunction "P-_P$2") (pintype "bidirectional"))
      (node (ref "U304") (pin "P$1") (pinfunction "P-_P$1") (pintype "bidirectional"))
      (node (ref "U304") (pin "P$2") (pinfunction "P-_P$2") (pintype "bidirectional"))
      (node (ref "V2") (pin "2") (pinfunction "S_2") (pintype "passive"))
      (node (ref "V302") (pin "2") (pinfunction "S_2") (pintype "passive"))
      (node (ref "V304") (pin "2") (pinfunction "S_2") (pintype "passive"))
      (node (ref "V401") (pin "2") (pinfunction "S_2") (pintype "passive"))
      (node (ref "X102") (pin "4") (pinfunction "GND_4") (pintype "passive"))
      (node (ref "X302") (pin "A1") (pinfunction "GND_A1") (pintype "bidirectional"))
      (node (ref "X302") (pin "A12") (pinfunction "GND_A12") (pintype "bidirectional"))
      (node (ref "X302") (pin "B1") (pinfunction "GND_B1") (pintype "bidirectional"))
      (node (ref "X302") (pin "B12") (pinfunction "GND_B12") (pintype "bidirectional"))
      (node (ref "X302") (pin "G3") (pinfunction "GND_G3") (pintype "bidirectional"))
      (node (ref "X302") (pin "G4") (pinfunction "GND_G4") (pintype "bidirectional"))
      (node (ref "X302") (pin "Z1") (pinfunction "SHIELD_Z1") (pintype "bidirectional"))
      (node (ref "X302") (pin "Z2") (pinfunction "SHIELD_Z2") (pintype "bidirectional"))
      (node (ref "X302") (pin "Z3") (pinfunction "SHIELD_Z3") (pintype "bidirectional"))
      (node (ref "X302") (pin "Z4") (pinfunction "SHIELD_Z4") (pintype "bidirectional"))
      (node (ref "X302") (pin "Z5") (pinfunction "SHIELD_Z5") (pintype "bidirectional"))
      (node (ref "X302") (pin "Z6") (pinfunction "SHIELD_Z6") (pintype "bidirectional"))
      (node (ref "X7") (pin "1") (pinfunction "IN_1") (pintype "bidirectional"))
    )
    (net (code "35") (name "MICBIAS") (class "Default")
      (node (ref "C57") (pin "2") (pinfunction "2_2") (pintype "passive"))
      (node (ref "M1") (pin "15") (pinfunction "MICBIAS_15") (pintype "power_in"))
    )
    (net (code "36") (name "NF1") (class "Default")
      (node (ref "IC1") (pin "1") (pinfunction "COM_1") (pintype "passive"))
      (node (ref "N2") (pin "6") (pinfunction "IN-_6") (pintype "input"))
      (node (ref "N2") (pin "7") (pinfunction "OUT_7") (pintype "output"))
      (node (ref "R208") (pin "2") (pinfunction "2_2") (pintype "passive"))
    )
    (net (code "37") (name "NF2") (class "Default")
      (node (ref "D8") (pin "1") (pinfunction "P$1_1") (pintype "bidirectional"))
      (node (ref "IC2") (pin "1") (pinfunction "COM_1") (pintype "passive"))
      (node (ref "L10") (pin "1") (pinfunction "1_1") (pintype "passive"))
      (node (ref "L11") (pin "1") (pinfunction "1_1") (pintype "passive"))
      (node (ref "R10") (pin "1") (pinfunction "1_1") (pintype "passive"))
      (node (ref "V1") (pin "3") (pinfunction "D_3") (pintype "passive"))
    )
    (net (code "38") (name "Net-(C1-Pad1)") (class "Default")
      (node (ref "C1") (pin "1") (pinfunction "1_1") (pintype "passive"))
      (node (ref "L1") (pin "1") (pinfunction "1_1") (pintype "passive"))
      (node (ref "TP1") (pin "TP") (pinfunction "TP_TP") (pintype "input"))
    )
    (net (code "39") (name "Net-(C3B-1)") (class "Default")
      (node (ref "C3") (pin "3") (pinfunction "1_3") (pintype "passive"))
      (node (ref "H201") (pin "P$13") (pinfunction "T3_P$13") (pintype "bidirectional"))
      (node (ref "R1") (pin "13") (pinfunction "1_13") (pintype "passive"))
    )
    (net (code "40") (name "Net-(C3C-1)") (class "Default")
      (node (ref "C3") (pin "5") (pinfunction "1_5") (pintype "passive"))
      (node (ref "H201") (pin "P$12") (pinfunction "T4_P$12") (pintype "bidirectional"))
      (node (ref "R1") (pin "11") (pinfunction "1_11") (pintype "passive"))
    )
    (net (code "41") (name "Net-(C3D-1)") (class "Default")
      (node (ref "C3") (pin "7") (pinfunction "1_7") (pintype "passive"))
      (node (ref "H201") (pin "P$9") (pinfunction "B0_P$9") (pintype "bidirectional"))
      (node (ref "R1") (pin "9") (pinfunction "1_9") (pintype "passive"))
    )
    (net (code "42") (name "Net-(C4B-1)") (class "Default")
      (node (ref "C4") (pin "3") (pinfunction "1_3") (pintype "passive"))
      (node (ref "H201") (pin "P$8") (pinfunction "B2_P$8") (pintype "bidirectional"))
      (node (ref "R1") (pin "5") (pinfunction "1_5") (pintype "passive"))
    )
    (net (code "43") (name "Net-(C4C-1)") (class "Default")
      (node (ref "C4") (pin "5") (pinfunction "1_5") (pintype "passive"))
      (node (ref "H201") (pin "P$6") (pinfunction "B3_P$6") (pintype "bidirectional"))
      (node (ref "R1") (pin "3") (pinfunction "1_3") (pintype "passive"))
    )
    (net (code "44") (name "Net-(C4D-1)") (class "Default")
      (node (ref "C4") (pin "7") (pinfunction "1_7") (pintype "passive"))
      (node (ref "H201") (pin "P$5") (pinfunction "B4_P$5") (pintype "bidirectional"))
      (node (ref "R1") (pin "1") (pinfunction "1_1") (pintype "passive"))
    )
    (net (code "45") (name "Net-(C5B-1)") (class "Default")
      (node (ref "C5") (pin "3") (pinfunction "1_3") (pintype "passive"))
      (node (ref "H201") (pin "P$1") (pinfunction "COM_P$1") (pintype "bidirectional"))
      (node (ref "R2") (pin "13") (pinfunction "1_13") (pintype "passive"))
    )
    (net (code "46") (name "Net-(C5C-1)") (class "Default")
      (node (ref "C5") (pin "5") (pinfunction "1_5") (pintype "passive"))
      (node (ref "H201") (pin "P$19") (pinfunction "2A_P$19") (pintype "bidirectional"))
      (node (ref "R2") (pin "11") (pinfunction "1_11") (pintype "passive"))
    )
    (net (code "47") (name "Net-(C5D-1)") (class "Default")
      (node (ref "C5") (pin "7") (pinfunction "1_7") (pintype "passive"))
      (node (ref "H201") (pin "P$18") (pinfunction "2B_P$18") (pintype "bidirectional"))
      (node (ref "R2") (pin "9") (pinfunction "1_9") (pintype "passive"))
    )
    (net (code "48") (name "Net-(C6B-2)") (class "Default")
      (node (ref "C6") (pin "4") (pinfunction "2_4") (pintype "passive"))
      (node (ref "H201") (pin "P$23") (pinfunction "1A_P$23") (pintype "bidirectional"))
      (node (ref "R3") (pin "11") (pinfunction "1_11") (pintype "passive"))
    )
    (net (code "49") (name "Net-(C6C-2)") (class "Default")
      (node (ref "C6") (pin "6") (pinfunction "2_6") (pintype "passive"))
      (node (ref "H201") (pin "P$11") (pinfunction "T2_P$11") (pintype "bidirectional"))
      (node (ref "R3") (pin "13") (pinfunction "1_13") (pintype "passive"))
    )
    (net (code "50") (name "Net-(C6D-2)") (class "Default")
      (node (ref "C6") (pin "8") (pinfunction "2_8") (pintype "passive"))
      (node (ref "H201") (pin "P$10") (pinfunction "T1_P$10") (pintype "bidirectional"))
      (node (ref "R3") (pin "15") (pinfunction "1_15") (pintype "passive"))
    )
    (net (code "51") (name "Net-(C7B-2)") (class "Default")
      (node (ref "C7") (pin "4") (pinfunction "2_4") (pintype "passive"))
      (node (ref "H201") (pin "P$2") (pinfunction "1E_P$2") (pintype "bidirectional"))
      (node (ref "R3") (pin "3") (pinfunction "1_3") (pintype "passive"))
    )
    (net (code "52") (name "Net-(C7C-2)") (class "Default")
      (node (ref "C7") (pin "6") (pinfunction "2_6") (pintype "passive"))
      (node (ref "H201") (pin "P$3") (pinfunction "1D_P$3") (pintype "bidirectional"))
      (node (ref "R3") (pin "5") (pinfunction "1_5") (pintype "passive"))
    )
    (net (code "53") (name "Net-(C7D-2)") (class "Default")
      (node (ref "C7") (pin "8") (pinfunction "2_8") (pintype "passive"))
      (node (ref "H201") (pin "P$4") (pinfunction "1C_P$4") (pintype "bidirectional"))
      (node (ref "R3") (pin "7") (pinfunction "1_7") (pintype "passive"))
    )
    (net (code "54") (name "Net-(C8B-2)") (class "Default")
      (node (ref "C8") (pin "4") (pinfunction "2_4") (pintype "passive"))
      (node (ref "H201") (pin "P$14") (pinfunction "2E_P$14") (pintype "bidirectional"))
      (node (ref "R2") (pin "3") (pinfunction "1_3") (pintype "passive"))
    )
    (net (code "55") (name "Net-(C8C-2)") (class "Default")
      (node (ref "C8") (pin "6") (pinfunction "2_6") (pintype "passive"))
      (node (ref "H201") (pin "P$15") (pinfunction "2D_P$15") (pintype "bidirectional"))
      (node (ref "R2") (pin "5") (pinfunction "1_5") (pintype "passive"))
    )
    (net (code "56") (name "Net-(C8D-2)") (class "Default")
      (node (ref "C8") (pin "8") (pinfunction "2_8") (pintype "passive"))
      (node (ref "H201") (pin "P$16") (pinfunction "2C_P$16") (pintype "bidirectional"))
      (node (ref "R2") (pin "7") (pinfunction "1_7") (pintype "passive"))
    )
    (net (code "57") (name "Net-(C11-Pad1)") (class "Default")
      (node (ref "C11") (pin "1") (pinfunction "1_1") (pintype "passive"))
      (node (ref "C12") (pin "1") (pinfunction "1_1") (pintype "passive"))
      (node (ref "R5") (pin "1") (pinfunction "1_1") (pintype "passive"))
    )
    (net (code "58") (name "Net-(C27-Pad1)") (class "Default")
      (node (ref "C27") (pin "1") (pinfunction "1_1") (pintype "passive"))
      (node (ref "R11") (pin "1") (pinfunction "1_1") (pintype "passive"))
      (node (ref "R4") (pin "2") (pinfunction "2_2") (pintype "passive"))
    )
    (net (code "59") (name "Net-(C32-Pad1)") (class "Default")
      (node (ref "C32") (pin "1") (pinfunction "1_1") (pintype "passive"))
      (node (ref "R26") (pin "2") (pinfunction "2_2") (pintype "passive"))
      (node (ref "R27") (pin "1") (pinfunction "1_1") (pintype "passive"))
    )
    (net (code "60") (name "Net-(C34-Pad1)") (class "Default")
      (node (ref "C34") (pin "1") (pinfunction "1_1") (pintype "passive"))
      (node (ref "D404") (pin "A") (pinfunction "A_A") (pintype "passive"))
      (node (ref "L5") (pin "2") (pinfunction "2_2") (pintype "passive"))
    )
    (net (code "61") (name "Net-(C35-Pad1)") (class "Default")
      (node (ref "C35") (pin "1") (pinfunction "1_1") (pintype "passive"))
      (node (ref "C409") (pin "1") (pinfunction "1_1") (pintype "passive"))
      (node (ref "C48") (pin "1") (pinfunction "1_1") (pintype "passive"))
      (node (ref "D404") (pin "C") (pinfunction "C_C") (pintype "passive"))
      (node (ref "L6") (pin "1") (pinfunction "1_1") (pintype "passive"))
      (node (ref "R407") (pin "2") (pinfunction "2_2") (pintype "passive"))
    )
    (net (code "62") (name "Net-(C36-Pad2)") (class "Default")
      (node (ref "C36") (pin "2") (pinfunction "2_2") (pintype "passive"))
      (node (ref "C407") (pin "2") (pinfunction "2_2") (pintype "passive"))
      (node (ref "C49") (pin "2") (pinfunction "2_2") (pintype "passive"))
      (node (ref "L405") (pin "2") (pinfunction "2_2") (pintype "passive"))
      (node (ref "L9") (pin "1") (pinfunction "1_1") (pintype "passive"))
      (node (ref "R406") (pin "1") (pinfunction "1_1") (pintype "passive"))
    )
    (net (code "63") (name "Net-(C40-Pad1)") (class "Default")
      (node (ref "C40") (pin "1") (pinfunction "1_1") (pintype "passive"))
      (node (ref "TP4") (pin "TP") (pinfunction "TP_TP") (pintype "input"))
    )
    (net (code "64") (name "Net-(C47-Pad1)") (class "Default")
      (node (ref "C47") (pin "1") (pinfunction "1_1") (pintype "passive"))
      (node (ref "R19") (pin "1") (pinfunction "1_1") (pintype "passive"))
    )
    (net (code "65") (name "Net-(C51-+)") (class "Default")
      (node (ref "C403") (pin "1") (pinfunction "1_1") (pintype "passive"))
      (node (ref "C51") (pin "2+") (pinfunction "+_2+") (pintype "passive"))
      (node (ref "L403") (pin "1") (pinfunction "1_1") (pintype "passive"))
      (node (ref "L404") (pin "1") (pinfunction "1_1") (pintype "passive"))
      (node (ref "L7") (pin "2") (pinfunction "2_2") (pintype "passive"))
      (node (ref "N401") (pin "8") (pinfunction "V_IN_8") (pintype "bidirectional"))
      (node (ref "R402") (pin "2") (pinfunction "2_2") (pintype "passive"))
    )
    (net (code "66") (name "Net-(C63-Pad1)") (class "Default")
      (node (ref "C63") (pin "1") (pinfunction "1_1") (pintype "passive"))
      (node (ref "C65") (pin "2") (pinfunction "2_2") (pintype "passive"))
      (node (ref "C67") (pin "2") (pinfunction "2_2") (pintype "passive"))
      (node (ref "C68") (pin "1") (pinfunction "1_1") (pintype "passive"))
      (node (ref "L11") (pin "2") (pinfunction "2_2") (pintype "passive"))
      (node (ref "R45") (pin "2") (pinfunction "2_2") (pintype "passive"))
    )
    (net (code "67") (name "Net-(C64-Pad2)") (class "Default")
      (node (ref "C64") (pin "2") (pinfunction "2_2") (pintype "passive"))
      (node (ref "C66") (pin "2") (pinfunction "2_2") (pintype "passive"))
      (node (ref "C67") (pin "1") (pinfunction "1_1") (pintype "passive"))
      (node (ref "C69") (pin "2") (pinfunction "2_2") (pintype "passive"))
      (node (ref "L10") (pin "2") (pinfunction "2_2") (pintype "passive"))
      (node (ref "R46") (pin "1") (pinfunction "1_1") (pintype "passive"))
    )
    (net (code "68") (name "Net-(C201-Pad1)") (class "Default")
      (node (ref "C201") (pin "1") (pinfunction "1_1") (pintype "passive"))
      (node (ref "L201") (pin "1") (pinfunction "1_1") (pintype "passive"))
      (node (ref "TP201") (pin "TP") (pinfunction "TP_TP") (pintype "input"))
    )
    (net (code "69") (name "Net-(C205-Pad1)") (class "Default")
      (node (ref "C205") (pin "1") (pinfunction "1_1") (pintype "passive"))
      (node (ref "L202") (pin "1") (pinfunction "1_1") (pintype "passive"))
      (node (ref "TP204") (pin "TP") (pinfunction "TP_TP") (pintype "input"))
    )
    (net (code "70") (name "Net-(C206-Pad1)") (class "Default")
      (node (ref "C206") (pin "1") (pinfunction "1_1") (pintype "passive"))
      (node (ref "L203") (pin "1") (pinfunction "1_1") (pintype "passive"))
      (node (ref "TP205") (pin "TP") (pinfunction "TP_TP") (pintype "input"))
    )
    (net (code "71") (name "Net-(C212-Pad1)") (class "Default")
      (node (ref "C212") (pin "1") (pinfunction "1_1") (pintype "passive"))
      (node (ref "L204") (pin "1") (pinfunction "1_1") (pintype "passive"))
      (node (ref "TP206") (pin "TP") (pinfunction "TP_TP") (pintype "input"))
    )
    (net (code "72") (name "Net-(C220-Pad2)") (class "Default")
      (node (ref "C220") (pin "2") (pinfunction "2_2") (pintype "passive"))
      (node (ref "R209") (pin "1") (pinfunction "1_1") (pintype "passive"))
    )
    (net (code "73") (name "Net-(C221-Pad1)") (class "Default")
      (node (ref "C221") (pin "1") (pinfunction "1_1") (pintype "passive"))
      (node (ref "C224") (pin "1") (pinfunction "1_1") (pintype "passive"))
      (node (ref "L209") (pin "1") (pinfunction "1_1") (pintype "passive"))
      (node (ref "R212") (pin "2") (pinfunction "2_2") (pintype "passive"))
    )
    (net (code "74") (name "Net-(C405-Pad1)") (class "Default")
      (node (ref "C405") (pin "1") (pinfunction "1_1") (pintype "passive"))
      (node (ref "D403") (pin "A") (pinfunction "A_A") (pintype "passive"))
      (node (ref "L405") (pin "1") (pinfunction "1_1") (pintype "passive"))
    )
    (net (code "75") (name "Net-(D1--)") (class "Default")
      (node (ref "D1") (pin "1") (pinfunction "-_1") (pintype "passive"))
      (node (ref "D2") (pin "1") (pinfunction "-_1") (pintype "passive"))
      (node (ref "R401") (pin "2") (pinfunction "2_2") (pintype "passive"))
    )
    (net (code "76") (name "Net-(D3-C)") (class "Default")
      (node (ref "C40") (pin "2") (pinfunction "2_2") (pintype "passive"))
      (node (ref "C41") (pin "1") (pinfunction "1_1") (pintype "passive"))
      (node (ref "D3") (pin "K") (pinfunction "C_K") (pintype "passive"))
      (node (ref "D4") (pin "A") (pinfunction "A_A") (pintype "passive"))
      (node (ref "N6") (pin "2") (pinfunction "IN-_2") (pintype "input"))
      (node (ref "R18") (pin "2") (pinfunction "2_2") (pintype "passive"))
    )
    (net (code "77") (name "Net-(D4-C)") (class "Default")
      (node (ref "C39") (pin "1") (pinfunction "1_1") (pintype "passive"))
      (node (ref "D3") (pin "A") (pinfunction "A_A") (pintype "passive"))
      (node (ref "D4") (pin "K") (pinfunction "C_K") (pintype "passive"))
      (node (ref "N6") (pin "3") (pinfunction "IN+_3") (pintype "input"))
      (node (ref "R17") (pin "2") (pinfunction "2_2") (pintype "passive"))
    )
    (net (code "78") (name "Net-(D301-A2)") (class "Default")
      (node (ref "D301") (pin "2") (pinfunction "A2_2") (pintype "passive"))
      (node (ref "R306") (pin "1") (pinfunction "1_1") (pintype "passive"))
      (node (ref "V302") (pin "3") (pinfunction "D_3") (pintype "passive"))
    )
    (net (code "79") (name "Net-(D301-AK)") (class "Default")
      (node (ref "D301") (pin "3") (pinfunction "AK_3") (pintype "passive"))
      (node (ref "S301") (pin "P3") (pinfunction "2_P3") (pintype "bidirectional"))
      (node (ref "S301") (pin "P4") (pinfunction "2_P4") (pintype "bidirectional"))
    )
    (net (code "80") (name "Net-(D302-Pad1)") (class "Default")
      (node (ref "D302") (pin "1") (pinfunction "1_1") (pintype "passive"))
      (node (ref "R308") (pin "1") (pinfunction "1_1") (pintype "passive"))
    )
    (net (code "81") (name "Net-(D302-Pad3)") (class "Default")
      (node (ref "D302") (pin "3") (pinfunction "3_3") (pintype "passive"))
      (node (ref "R307") (pin "1") (pinfunction "1_1") (pintype "passive"))
    )
    (net (code "82") (name "Net-(H201-1B)") (class "Default")
      (node (ref "C6") (pin "2") (pinfunction "2_2") (pintype "passive"))
      (node (ref "H201") (pin "P$22") (pinfunction "1B_P$22") (pintype "bidirectional"))
      (node (ref "R3") (pin "9") (pinfunction "1_9") (pintype "passive"))
    )
    (net (code "83") (name "Net-(H201-1F)") (class "Default")
      (node (ref "C7") (pin "2") (pinfunction "2_2") (pintype "passive"))
      (node (ref "H201") (pin "P$24") (pinfunction "1F_P$24") (pintype "bidirectional"))
      (node (ref "R3") (pin "1") (pinfunction "1_1") (pintype "passive"))
    )
    (net (code "84") (name "Net-(H201-1G)") (class "Default")
      (node (ref "C5") (pin "1") (pinfunction "1_1") (pintype "passive"))
      (node (ref "H201") (pin "P$21") (pinfunction "1G_P$21") (pintype "bidirectional"))
      (node (ref "R2") (pin "15") (pinfunction "1_15") (pintype "passive"))
    )
    (net (code "85") (name "Net-(H201-2F)") (class "Default")
      (node (ref "C8") (pin "2") (pinfunction "2_2") (pintype "passive"))
      (node (ref "H201") (pin "P$20") (pinfunction "2F_P$20") (pintype "bidirectional"))
      (node (ref "R2") (pin "1") (pinfunction "1_1") (pintype "passive"))
    )
    (net (code "86") (name "Net-(H201-2G)") (class "Default")
      (node (ref "C3") (pin "1") (pinfunction "1_1") (pintype "passive"))
      (node (ref "H201") (pin "P$17") (pinfunction "2G_P$17") (pintype "bidirectional"))
      (node (ref "R1") (pin "15") (pinfunction "1_15") (pintype "passive"))
    )
    (net (code "87") (name "Net-(H201-B1)") (class "Default")
      (node (ref "C4") (pin "1") (pinfunction "1_1") (pintype "passive"))
      (node (ref "H201") (pin "P$7") (pinfunction "B1_P$7") (pintype "bidirectional"))
      (node (ref "R1") (pin "7") (pinfunction "1_7") (pintype "passive"))
    )
    (net (code "88") (name "Net-(H401-C)") (class "Default")
      (node (ref "H401") (pin "K") (pinfunction "C_K") (pintype "passive"))
      (node (ref "R403") (pin "2") (pinfunction "2_2") (pintype "passive"))
    )
    (net (code "89") (name "Net-(IC1A-IN)") (class "Default")
      (node (ref "C26") (pin "1") (pinfunction "1_1") (pintype "passive"))
      (node (ref "IC1") (pin "6") (pinfunction "IN_6") (pintype "input"))
      (node (ref "IC2") (pin "6") (pinfunction "IN_6") (pintype "input"))
      (node (ref "L3") (pin "1") (pinfunction "1_1") (pintype "passive"))
    )
    (net (code "90") (name "Net-(IC1A-NC)") (class "Default")
      (node (ref "IC1") (pin "2") (pinfunction "NC_2") (pintype "passive"))
      (node (ref "IC2") (pin "2") (pinfunction "NC_2") (pintype "passive"))
      (node (ref "R9") (pin "1") (pinfunction "1_1") (pintype "passive"))
    )
    (net (code "91") (name "Net-(IC1A-NO)") (class "Default")
      (node (ref "IC1") (pin "8") (pinfunction "NO_8") (pintype "passive"))
      (node (ref "IC3") (pin "1") (pinfunction "COM_1") (pintype "passive"))
    )
    (net (code "92") (name "Net-(IC2A-NO)") (class "Default")
      (node (ref "IC2") (pin "8") (pinfunction "NO_8") (pintype "passive"))
      (node (ref "IC4") (pin "1") (pinfunction "COM_1") (pintype "passive"))
    )
    (net (code "93") (name "Net-(IC3A-IN)") (class "Default")
      (node (ref "C10") (pin "1") (pinfunction "1_1") (pintype "passive"))
      (node (ref "IC3") (pin "6") (pinfunction "IN_6") (pintype "input"))
      (node (ref "IC4") (pin "6") (pinfunction "IN_6") (pintype "input"))
      (node (ref "L2") (pin "1") (pinfunction "1_1") (pintype "passive"))
    )
    (net (code "94") (name "Net-(IC3A-NC)") (class "Default")
      (node (ref "IC3") (pin "2") (pinfunction "NC_2") (pintype "passive"))
      (node (ref "R11") (pin "2") (pinfunction "2_2") (pintype "passive"))
    )
    (net (code "95") (name "Net-(IC3A-NO)") (class "Default")
      (node (ref "C11") (pin "2") (pinfunction "2_2") (pintype "passive"))
      (node (ref "IC3") (pin "8") (pinfunction "NO_8") (pintype "passive"))
    )
    (net (code "96") (name "Net-(IC4A-NC)") (class "Default")
      (node (ref "C28") (pin "2") (pinfunction "2_2") (pintype "passive"))
      (node (ref "IC4") (pin "2") (pinfunction "NC_2") (pintype "passive"))
      (node (ref "R12") (pin "1") (pinfunction "1_1") (pintype "passive"))
    )
    (net (code "97") (name "Net-(IC4A-NO)") (class "Default")
      (node (ref "C14") (pin "2") (pinfunction "2_2") (pintype "passive"))
      (node (ref "IC4") (pin "8") (pinfunction "NO_8") (pintype "passive"))
      (node (ref "R8") (pin "1") (pinfunction "1_1") (pintype "passive"))
    )
    (net (code "98") (name "Net-(IC201A-COM)") (class "Default")
      (node (ref "IC201") (pin "1") (pinfunction "COM_1") (pintype "passive"))
      (node (ref "R27") (pin "2") (pinfunction "2_2") (pintype "passive"))
    )
    (net (code "99") (name "Net-(IC201A-IN)") (class "Default")
      (node (ref "C214") (pin "1") (pinfunction "1_1") (pintype "passive"))
      (node (ref "IC201") (pin "6") (pinfunction "IN_6") (pintype "input"))
      (node (ref "L205") (pin "1") (pinfunction "1_1") (pintype "passive"))
    )
    (net (code "100") (name "Net-(IC201A-NC)") (class "Default")
      (node (ref "C42") (pin "2") (pinfunction "2_2") (pintype "passive"))
      (node (ref "IC201") (pin "2") (pinfunction "NC_2") (pintype "passive"))
      (node (ref "N7") (pin "6") (pinfunction "OUT_6") (pintype "output"))
      (node (ref "R20") (pin "1") (pinfunction "1_1") (pintype "passive"))
      (node (ref "R7") (pin "1") (pinfunction "1_1") (pintype "passive"))
    )
    (net (code "101") (name "Net-(IC201A-NO)") (class "Default")
      (node (ref "C208") (pin "1") (pinfunction "1_1") (pintype "passive"))
      (node (ref "IC201") (pin "8") (pinfunction "NO_8") (pintype "passive"))
      (node (ref "L202") (pin "2") (pinfunction "2_2") (pintype "passive"))
      (node (ref "R203") (pin "1") (pinfunction "1_1") (pintype "passive"))
    )
    (net (code "102") (name "Net-(N1A-IN+)") (class "Default")
      (node (ref "C13") (pin "2") (pinfunction "2_2") (pintype "passive"))
      (node (ref "N1") (pin "3") (pinfunction "IN+_3") (pintype "input"))
      (node (ref "R4") (pin "1") (pinfunction "1_1") (pintype "passive"))
    )
    (net (code "103") (name "Net-(N1A-IN-)") (class "Default")
      (node (ref "N1") (pin "2") (pinfunction "IN-_2") (pintype "input"))
      (node (ref "R13") (pin "2") (pinfunction "2_2") (pintype "passive"))
      (node (ref "R14") (pin "2") (pinfunction "2_2") (pintype "passive"))
    )
    (net (code "104") (name "Net-(N1A-OUT)") (class "Default")
      (node (ref "C27") (pin "2") (pinfunction "2_2") (pintype "passive"))
      (node (ref "N1") (pin "1") (pinfunction "OUT_1") (pintype "output"))
      (node (ref "R12") (pin "2") (pinfunction "2_2") (pintype "passive"))
      (node (ref "R13") (pin "1") (pinfunction "1_1") (pintype "passive"))
    )
    (net (code "105") (name "Net-(N1B-IN+)") (class "Default")
      (node (ref "C12") (pin "2") (pinfunction "2_2") (pintype "passive"))
      (node (ref "N1") (pin "5") (pinfunction "IN+_5") (pintype "input"))
      (node (ref "R6") (pin "2") (pinfunction "2_2") (pintype "passive"))
    )
    (net (code "106") (name "Net-(N1B-IN-)") (class "Default")
      (node (ref "N1") (pin "6") (pinfunction "IN-_6") (pintype "input"))
      (node (ref "R15") (pin "2") (pinfunction "2_2") (pintype "passive"))
      (node (ref "R16") (pin "2") (pinfunction "2_2") (pintype "passive"))
    )
    (net (code "107") (name "Net-(N1B-OUT)") (class "Default")
      (node (ref "C14") (pin "1") (pinfunction "1_1") (pintype "passive"))
      (node (ref "N1") (pin "7") (pinfunction "OUT_7") (pintype "output"))
      (node (ref "R15") (pin "1") (pinfunction "1_1") (pintype "passive"))
      (node (ref "R5") (pin "2") (pinfunction "2_2") (pintype "passive"))
    )
    (net (code "108") (name "Net-(N2A-IN+)") (class "Default")
      (node (ref "C31") (pin "2") (pinfunction "2_2") (pintype "passive"))
      (node (ref "N2") (pin "3") (pinfunction "IN+_3") (pintype "input"))
      (node (ref "R26") (pin "1") (pinfunction "1_1") (pintype "passive"))
    )
    (net (code "109") (name "Net-(N2A-IN-)") (class "Default")
      (node (ref "N2") (pin "2") (pinfunction "IN-_2") (pintype "input"))
      (node (ref "R29") (pin "2") (pinfunction "2_2") (pintype "passive"))
      (node (ref "R30") (pin "2") (pinfunction "2_2") (pintype "passive"))
    )
    (net (code "110") (name "Net-(N2A-OUT)") (class "Default")
      (node (ref "C32") (pin "2") (pinfunction "2_2") (pintype "passive"))
      (node (ref "N2") (pin "1") (pinfunction "OUT_1") (pintype "output"))
      (node (ref "R28") (pin "2") (pinfunction "2_2") (pintype "passive"))
      (node (ref "R29") (pin "1") (pinfunction "1_1") (pintype "passive"))
    )
    (net (code "111") (name "Net-(N2C-IN+)") (class "Default")
      (node (ref "C33") (pin "2") (pinfunction "2_2") (pintype "passive"))
      (node (ref "N2") (pin "5") (pinfunction "IN+_5") (pintype "input"))
      (node (ref "R28") (pin "1") (pinfunction "1_1") (pintype "passive"))
    )
    (net (code "112") (name "Net-(N5A-IN+)") (class "Default")
      (node (ref "C215") (pin "1") (pinfunction "1_1") (pintype "passive"))
      (node (ref "N5") (pin "3") (pinfunction "IN+_3") (pintype "input"))
      (node (ref "R208") (pin "1") (pinfunction "1_1") (pintype "passive"))
    )
    (net (code "113") (name "Net-(N5A-IN-)") (class "Default")
      (node (ref "N5") (pin "4") (pinfunction "IN-_4") (pintype "input"))
      (node (ref "R209") (pin "2") (pinfunction "2_2") (pintype "passive"))
      (node (ref "R210") (pin "2") (pinfunction "2_2") (pintype "passive"))
    )
    (net (code "114") (name "Net-(N5A-OUT)") (class "Default")
      (node (ref "C221") (pin "2") (pinfunction "2_2") (pintype "passive"))
      (node (ref "N5") (pin "1") (pinfunction "OUT_1") (pintype "output"))
      (node (ref "R210") (pin "1") (pinfunction "1_1") (pintype "passive"))
    )
    (net (code "115") (name "Net-(N6A-OUT)") (class "Default")
      (node (ref "C41") (pin "2") (pinfunction "2_2") (pintype "passive"))
      (node (ref "N6") (pin "6") (pinfunction "OUT_6") (pintype "output"))
      (node (ref "R18") (pin "1") (pinfunction "1_1") (pintype "passive"))
      (node (ref "R19") (pin "2") (pinfunction "2_2") (pintype "passive"))
    )
    (net (code "116") (name "Net-(N7A-IN-)") (class "Default")
      (node (ref "C42") (pin "1") (pinfunction "1_1") (pintype "passive"))
      (node (ref "C47") (pin "2") (pinfunction "2_2") (pintype "passive"))
      (node (ref "N7") (pin "2") (pinfunction "IN-_2") (pintype "input"))
      (node (ref "R20") (pin "2") (pinfunction "2_2") (pintype "passive"))
    )
    (net (code "117") (name "Net-(N301-ISET)") (class "Default")
      (node (ref "N301") (pin "2") (pinfunction "ISET_2") (pintype "bidirectional"))
      (node (ref "R302") (pin "2") (pinfunction "2_2") (pintype "passive"))
    )
    (net (code "118") (name "Net-(N301-PRE)") (class "Default")
      (node (ref "N301") (pin "4") (pinfunction "PRE_4") (pintype "bidirectional"))
      (node (ref "R303") (pin "2") (pinfunction "2_2") (pintype "passive"))
    )
    (net (code "119") (name "Net-(N301-TS)") (class "Default")
      (node (ref "N301") (pin "9") (pinfunction "TS_9") (pintype "bidirectional"))
      (node (ref "R312") (pin "P$2") (pinfunction "2_P$2") (pintype "passive"))
      (node (ref "R313") (pin "P$2") (pinfunction "2_P$2") (pintype "passive"))
    )
    (net (code "120") (name "Net-(N301-VIN)") (class "Default")
      (node (ref "C301") (pin "1") (pinfunction "1_1") (pintype "passive"))
      (node (ref "C302") (pin "1") (pinfunction "1_1") (pintype "passive"))
      (node (ref "N301") (pin "1") (pinfunction "VIN_1") (pintype "input"))
      (node (ref "TP301") (pin "TP") (pinfunction "TP_TP") (pintype "input"))
      (node (ref "X302") (pin "A4") (pinfunction "VBUS_A4") (pintype "bidirectional"))
      (node (ref "X302") (pin "A9") (pinfunction "VBUS_A9") (pintype "bidirectional"))
      (node (ref "X302") (pin "B4") (pinfunction "VBUS_B4") (pintype "bidirectional"))
      (node (ref "X302") (pin "B9") (pinfunction "VBUS_B9") (pintype "bidirectional"))
    )
    (net (code "121") (name "Net-(N301-~{CHG})") (class "Default")
      (node (ref "N301") (pin "8") (pinfunction "~{CHG}_8") (pintype "output"))
      (node (ref "R308") (pin "2") (pinfunction "2_2") (pintype "passive"))
    )
    (net (code "122") (name "Net-(N301-~{PG})") (class "Default")
      (node (ref "N301") (pin "5") (pinfunction "~{PG}_5") (pintype "output"))
      (node (ref "R307") (pin "2") (pinfunction "2_2") (pintype "passive"))
    )
    (net (code "123") (name "Net-(N302-EN)") (class "Default")
      (node (ref "N302") (pin "6") (pinfunction "EN_6") (pintype "bidirectional"))
      (node (ref "R316") (pin "2") (pinfunction "2_2") (pintype "passive"))
    )
    (net (code "124") (name "Net-(N302-PVIN)") (class "Default")
      (node (ref "C304") (pin "1") (pinfunction "1_1") (pintype "bidirectional"))
      (node (ref "N302") (pin "5") (pinfunction "PVIN_5") (pintype "bidirectional"))
      (node (ref "N302") (pin "7") (pinfunction "VIN_7") (pintype "bidirectional"))
      (node (ref "R311") (pin "2") (pinfunction "2_2") (pintype "passive"))
      (node (ref "R316") (pin "1") (pinfunction "1_1") (pintype "passive"))
      (node (ref "V301") (pin "3") (pinfunction "D_3") (pintype "passive"))
    )
    (net (code "125") (name "Net-(N302-SW1)") (class "Default")
      (node (ref "L301") (pin "1") (pinfunction "1_1") (pintype "passive"))
      (node (ref "N302") (pin "4") (pinfunction "SW1_4") (pintype "bidirectional"))
    )
    (net (code "126") (name "Net-(N302-SW2)") (class "Default")
      (node (ref "L301") (pin "2") (pinfunction "2_2") (pintype "passive"))
      (node (ref "N302") (pin "2") (pinfunction "SW2_2") (pintype "bidirectional"))
    )
    (net (code "127") (name "Net-(N401-FB1N)") (class "Default")
      (node (ref "C409") (pin "2") (pinfunction "2_2") (pintype "passive"))
      (node (ref "N401") (pin "1") (pinfunction "FB1N_1") (pintype "bidirectional"))
      (node (ref "R407") (pin "1") (pinfunction "1_1") (pintype "passive"))
      (node (ref "R408") (pin "2") (pinfunction "2_2") (pintype "passive"))
    )
    (net (code "128") (name "Net-(N401-FB1P)") (class "Default")
      (node (ref "C406") (pin "1") (pinfunction "1_1") (pintype "passive"))
      (node (ref "N401") (pin "2") (pinfunction "FB1P_2") (pintype "bidirectional"))
      (node (ref "N401") (pin "3") (pinfunction "VREF_3") (pintype "bidirectional"))
      (node (ref "R405") (pin "2") (pinfunction "2_2") (pintype "passive"))
    )
    (net (code "129") (name "Net-(N401-FB2P)") (class "Default")
      (node (ref "C407") (pin "1") (pinfunction "1_1") (pintype "passive"))
      (node (ref "N401") (pin "4") (pinfunction "FB2P_4") (pintype "bidirectional"))
      (node (ref "R405") (pin "1") (pinfunction "1_1") (pintype "passive"))
      (node (ref "R406") (pin "2") (pinfunction "2_2") (pintype "passive"))
    )
    (net (code "130") (name "Net-(N401-SW1)") (class "Default")
      (node (ref "C34") (pin "2") (pinfunction "2_2") (pintype "passive"))
      (node (ref "L403") (pin "2") (pinfunction "2_2") (pintype "passive"))
      (node (ref "N401") (pin "10") (pinfunction "SW1_10") (pintype "bidirectional"))
    )
    (net (code "131") (name "Net-(N401-SW2)") (class "Default")
      (node (ref "C405") (pin "2") (pinfunction "2_2") (pintype "passive"))
      (node (ref "L404") (pin "2") (pinfunction "2_2") (pintype "passive"))
      (node (ref "N401") (pin "6") (pinfunction "SW2_6") (pintype "bidirectional"))
    )
    (net (code "132") (name "Net-(N401-~{SHDN1})") (class "Default")
      (node (ref "C404") (pin "1") (pinfunction "1_1") (pintype "passive"))
      (node (ref "N401") (pin "7") (pinfunction "~{SHDN2}_7") (pintype "bidirectional"))
      (node (ref "N401") (pin "9") (pinfunction "~{SHDN1}_9") (pintype "bidirectional"))
      (node (ref "R402") (pin "1") (pinfunction "1_1") (pintype "passive"))
    )
    (net (code "133") (name "Net-(N404-NR)") (class "Default")
      (node (ref "C418") (pin "1") (pinfunction "1_1") (pintype "passive"))
      (node (ref "N404") (pin "4") (pinfunction "NR_4") (pintype "bidirectional"))
    )
    (net (code "134") (name "Net-(R301-Pad2)") (class "Default")
      (node (ref "R301") (pin "2") (pinfunction "2_2") (pintype "passive"))
      (node (ref "R302") (pin "1") (pinfunction "1_1") (pintype "passive"))
    )
    (net (code "135") (name "Net-(R314-Pad1)") (class "Default")
      (node (ref "R314") (pin "1") (pinfunction "1_1") (pintype "passive"))
      (node (ref "U301") (pin "P$1") (pinfunction "P+_P$1") (pintype "bidirectional"))
      (node (ref "U301") (pin "P$2") (pinfunction "P+_P$2") (pintype "bidirectional"))
    )
    (net (code "136") (name "Net-(R315-Pad1)") (class "Default")
      (node (ref "R315") (pin "1") (pinfunction "1_1") (pintype "passive"))
      (node (ref "U303") (pin "P$1") (pinfunction "P+_P$1") (pintype "bidirectional"))
      (node (ref "U303") (pin "P$2") (pinfunction "P+_P$2") (pintype "bidirectional"))
    )
    (net (code "137") (name "Net-(U101-PDI)") (class "Default")
      (node (ref "U101") (pin "56") (pinfunction "PDI_56") (pintype "bidirectional"))
      (node (ref "X102") (pin "2") (pinfunction "PDI_2") (pintype "passive"))
    )
    (net (code "138") (name "Net-(U101-~{RESET}{slash}PDI)") (class "Default")
      (node (ref "R101") (pin "1") (pinfunction "1_1") (pintype "passive"))
      (node (ref "U101") (pin "57") (pinfunction "~{RESET}/PDI_57") (pintype "bidirectional"))
      (node (ref "X102") (pin "3") (pinfunction "~{RES}_3") (pintype "passive"))
    )
    (net (code "139") (name "Net-(V1-G)") (class "Default")
      (node (ref "C30") (pin "1") (pinfunction "1_1") (pintype "passive"))
      (node (ref "L4") (pin "1") (pinfunction "1_1") (pintype "passive"))
      (node (ref "V1") (pin "1") (pinfunction "G_1") (pintype "passive"))
    )
    (net (code "140") (name "Net-(V2-D)") (class "Default")
      (node (ref "R403") (pin "1") (pinfunction "1_1") (pintype "passive"))
      (node (ref "V2") (pin "3") (pinfunction "D_3") (pintype "passive"))
    )
    (net (code "141") (name "Net-(V2-G)") (class "Default")
      (node (ref "R23") (pin "2") (pinfunction "2_2") (pintype "passive"))
      (node (ref "R25") (pin "2") (pinfunction "2_2") (pintype "passive"))
      (node (ref "V2") (pin "1") (pinfunction "G_1") (pintype "passive"))
    )
    (net (code "142") (name "Net-(V301-G)") (class "Default")
      (node (ref "R305") (pin "1") (pinfunction "1_1") (pintype "passive"))
      (node (ref "R306") (pin "2") (pinfunction "2_2") (pintype "passive"))
      (node (ref "V301") (pin "1") (pinfunction "G_1") (pintype "passive"))
    )
    (net (code "143") (name "Net-(V302-G)") (class "Default")
      (node (ref "R309") (pin "2") (pinfunction "2_2") (pintype "passive"))
      (node (ref "R310") (pin "2") (pinfunction "2_2") (pintype "passive"))
      (node (ref "V302") (pin "1") (pinfunction "G_1") (pintype "passive"))
    )
    (net (code "144") (name "Net-(V303-D)") (class "Default")
      (node (ref "R320") (pin "2") (pinfunction "2_2") (pintype "passive"))
      (node (ref "V303") (pin "3") (pinfunction "D_3") (pintype "passive"))
    )
    (net (code "145") (name "Net-(V303-G)") (class "Default")
      (node (ref "R317") (pin "1") (pinfunction "1_1") (pintype "passive"))
      (node (ref "R318") (pin "2") (pinfunction "2_2") (pintype "passive"))
      (node (ref "V303") (pin "1") (pinfunction "G_1") (pintype "passive"))
    )
    (net (code "146") (name "Net-(V304-D)") (class "Default")
      (node (ref "R318") (pin "1") (pinfunction "1_1") (pintype "passive"))
      (node (ref "V304") (pin "3") (pinfunction "D_3") (pintype "passive"))
    )
    (net (code "147") (name "Net-(V304-G)") (class "Default")
      (node (ref "R319") (pin "2") (pinfunction "2_2") (pintype "passive"))
      (node (ref "R321") (pin "2") (pinfunction "2_2") (pintype "passive"))
      (node (ref "V304") (pin "1") (pinfunction "G_1") (pintype "passive"))
    )
    (net (code "148") (name "Net-(V401-D)") (class "Default")
      (node (ref "R401") (pin "1") (pinfunction "1_1") (pintype "passive"))
      (node (ref "V401") (pin "3") (pinfunction "D_3") (pintype "passive"))
    )
    (net (code "149") (name "Net-(V401-G)") (class "Default")
      (node (ref "R21") (pin "2") (pinfunction "2_2") (pintype "passive"))
      (node (ref "R22") (pin "1") (pinfunction "1_1") (pintype "passive"))
      (node (ref "V401") (pin "1") (pinfunction "G_1") (pintype "passive"))
    )
    (net (code "150") (name "P2_6") (class "Default")
      (node (ref "M1") (pin "21") (pinfunction "P2_6_21") (pintype "bidirectional"))
      (node (ref "U101") (pin "6") (pinfunction "PB0_6") (pintype "bidirectional"))
    )
    (net (code "151") (name "P3_2") (class "Default")
      (node (ref "M1") (pin "20") (pinfunction "P3_2_20") (pintype "bidirectional"))
      (node (ref "U101") (pin "9") (pinfunction "PB3_9") (pintype "bidirectional"))
    )
    (net (code "152") (name "P3_4_UART_RTS") (class "Default")
      (node (ref "M1") (pin "31") (pinfunction "P3_4_31") (pintype "bidirectional"))
      (node (ref "U101") (pin "21") (pinfunction "PC5_21") (pintype "bidirectional"))
      (node (ref "X7") (pin "2") (pinfunction "OUT_2") (pintype "bidirectional"))
    )
    (net (code "153") (name "P3_7_UART_CTS") (class "Default")
      (node (ref "M1") (pin "48") (pinfunction "P3_7_48") (pintype "bidirectional"))
      (node (ref "U101") (pin "20") (pinfunction "PC4_20") (pintype "bidirectional"))
    )
    (net (code "154") (name "P8_5_UART_TXD") (class "Default")
      (node (ref "M1") (pin "30") (pinfunction "P8_5_30") (pintype "bidirectional"))
      (node (ref "U101") (pin "22") (pinfunction "PC6_22") (pintype "bidirectional"))
    )
    (net (code "155") (name "P8_6_UART_RXD") (class "Default")
      (node (ref "M1") (pin "29") (pinfunction "P8_6_29") (pintype "bidirectional"))
      (node (ref "U101") (pin "23") (pinfunction "PC7_23") (pintype "bidirectional"))
    )
    (net (code "156") (name "PA4") (class "Default")
      (node (ref "R321") (pin "1") (pinfunction "1_1") (pintype "passive"))
      (node (ref "U101") (pin "32") (pinfunction "PD6_32") (pintype "bidirectional"))
    )
    (net (code "157") (name "PA6") (class "Default")
      (node (ref "C218") (pin "1") (pinfunction "1_1") (pintype "passive"))
      (node (ref "L205") (pin "2") (pinfunction "2_2") (pintype "passive"))
      (node (ref "U101") (pin "11") (pinfunction "PB5_11") (pintype "bidirectional"))
    )
    (net (code "158") (name "PB1") (class "Default")
      (node (ref "C9") (pin "1") (pinfunction "1_1") (pintype "passive"))
      (node (ref "L2") (pin "2") (pinfunction "2_2") (pintype "passive"))
      (node (ref "U101") (pin "7") (pinfunction "PB1_7") (pintype "bidirectional"))
    )
    (net (code "159") (name "PD0") (class "Default")
      (node (ref "C29") (pin "1") (pinfunction "1_1") (pintype "passive"))
      (node (ref "L4") (pin "2") (pinfunction "2_2") (pintype "passive"))
      (node (ref "U101") (pin "26") (pinfunction "PD0_26") (pintype "bidirectional"))
    )
    (net (code "160") (name "PD1") (class "Default")
      (node (ref "R22") (pin "2") (pinfunction "2_2") (pintype "passive"))
      (node (ref "U101") (pin "27") (pinfunction "PD1_27") (pintype "bidirectional"))
    )
    (net (code "161") (name "PD2") (class "Default")
      (node (ref "C303") (pin "2") (pinfunction "2_2") (pintype "passive"))
      (node (ref "D301") (pin "1") (pinfunction "A1_1") (pintype "passive"))
      (node (ref "R304") (pin "1") (pinfunction "1_1") (pintype "passive"))
      (node (ref "U101") (pin "28") (pinfunction "PD2_28") (pintype "bidirectional"))
    )
    (net (code "162") (name "PD3") (class "Default")
      (node (ref "R310") (pin "1") (pinfunction "1_1") (pintype "passive"))
      (node (ref "U101") (pin "29") (pinfunction "PD3_29") (pintype "bidirectional"))
    )
    (net (code "163") (name "PD5") (class "Default")
      (node (ref "R25") (pin "1") (pinfunction "1_1") (pintype "passive"))
      (node (ref "U101") (pin "31") (pinfunction "PD5_31") (pintype "bidirectional"))
    )
    (net (code "164") (name "PD7") (class "Default")
      (node (ref "C25") (pin "1") (pinfunction "1_1") (pintype "passive"))
      (node (ref "L3") (pin "2") (pinfunction "2_2") (pintype "passive"))
      (node (ref "U101") (pin "12") (pinfunction "PB6_12") (pintype "bidirectional"))
    )
    (net (code "165") (name "PE") (class "Default")
      (node (ref "R24") (pin "1") (pinfunction "1_1") (pintype "passive"))
    )
    (net (code "166") (name "PWR") (class "Default")
      (node (ref "M1") (pin "26") (pinfunction "PWR_26") (pintype "input"))
      (node (ref "U101") (pin "4") (pinfunction "PA6_4") (pintype "bidirectional"))
    )
    (net (code "167") (name "RST_N") (class "Default")
      (node (ref "M1") (pin "43") (pinfunction "RST_N_43") (pintype "input"))
      (node (ref "U101") (pin "13") (pinfunction "PB7_13") (pintype "bidirectional"))
    )
    (net (code "168") (name "SDA_PC0") (class "Default")
      (node (ref "N101") (pin "14") (pinfunction "SDA_14") (pintype "bidirectional"))
      (node (ref "U101") (pin "16") (pinfunction "PC0_16") (pintype "bidirectional"))
    )
    (net (code "169") (name "SENSOR") (class "Default")
      (node (ref "C2") (pin "1") (pinfunction "1_1") (pintype "passive"))
      (node (ref "L1") (pin "2") (pinfunction "2_2") (pintype "passive"))
      (node (ref "U101") (pin "10") (pinfunction "PB4_10") (pintype "bidirectional"))
    )
    (net (code "170") (name "SYS_PWR") (class "Default")
      (node (ref "C56") (pin "2") (pinfunction "2_2") (pintype "passive"))
      (node (ref "M1") (pin "24") (pinfunction "SYS_PWR_24") (pintype "power_in"))
    )
    (net (code "171") (name "T1") (class "Default")
      (node (ref "R3") (pin "16") (pinfunction "2_16") (pintype "passive"))
      (node (ref "U101") (pin "33") (pinfunction "PD7_33") (pintype "bidirectional"))
    )
    (net (code "172") (name "T2") (class "Default")
      (node (ref "R3") (pin "14") (pinfunction "2_14") (pintype "passive"))
      (node (ref "U101") (pin "36") (pinfunction "PE0_36") (pintype "bidirectional"))
    )
    (net (code "173") (name "T3") (class "Default")
      (node (ref "R1") (pin "14") (pinfunction "2_14") (pintype "passive"))
      (node (ref "U101") (pin "58") (pinfunction "PR0_58") (pintype "bidirectional"))
    )
    (net (code "174") (name "T4") (class "Default")
      (node (ref "R1") (pin "12") (pinfunction "2_12") (pintype "passive"))
      (node (ref "U101") (pin "59") (pinfunction "PR1_59") (pintype "bidirectional"))
    )
    (net (code "175") (name "TAST2") (class "Default")
      (node (ref "R404") (pin "1") (pinfunction "1_1") (pintype "passive"))
      (node (ref "S401") (pin "P3") (pinfunction "2_P3") (pintype "bidirectional"))
      (node (ref "S401") (pin "P4") (pinfunction "2_P4") (pintype "bidirectional"))
      (node (ref "U101") (pin "8") (pinfunction "PB2_8") (pintype "bidirectional"))
    )
    (net (code "176") (name "VCC") (class "Default")
      (node (ref "C101") (pin "1") (pinfunction "1_1") (pintype "passive"))
      (node (ref "C102") (pin "1") (pinfunction "1_1") (pintype "passive"))
      (node (ref "C103") (pin "1") (pinfunction "1_1") (pintype "passive"))
      (node (ref "C104") (pin "1") (pinfunction "1_1") (pintype "passive"))
      (node (ref "C105") (pin "1") (pinfunction "1_1") (pintype "passive"))
      (node (ref "C106") (pin "1") (pinfunction "1_1") (pintype "passive"))
      (node (ref "C107") (pin "1") (pinfunction "1_1") (pintype "passive"))
      (node (ref "C108") (pin "1") (pinfunction "1_1") (pintype "passive"))
      (node (ref "C419") (pin "1") (pinfunction "1_1") (pintype "passive"))
      (node (ref "C52") (pin "2+") (pinfunction "+_2+") (pintype "passive"))
      (node (ref "L8") (pin "1") (pinfunction "1_1") (pintype "passive"))
      (node (ref "N101") (pin "5") (pinfunction "VDDIO_5") (pintype "power_in"))
      (node (ref "N101") (pin "8") (pinfunction "VDD_8") (pintype "power_in"))
      (node (ref "N404") (pin "5") (pinfunction "OUT_5") (pintype "power_in"))
      (node (ref "R101") (pin "2") (pinfunction "2_2") (pintype "passive"))
      (node (ref "R304") (pin "2") (pinfunction "2_2") (pintype "passive"))
      (node (ref "R404") (pin "2") (pinfunction "2_2") (pintype "passive"))
      (node (ref "U101") (pin "15") (pinfunction "VCC_15") (pintype "power_in"))
      (node (ref "U101") (pin "25") (pinfunction "VCC_25") (pintype "power_in"))
      (node (ref "U101") (pin "35") (pinfunction "VCC_35") (pintype "power_in"))
      (node (ref "U101") (pin "45") (pinfunction "VCC_45") (pintype "power_in"))
      (node (ref "U101") (pin "53") (pinfunction "VCC_53") (pintype "power_in"))
      (node (ref "U101") (pin "61") (pinfunction "AVCC_61") (pintype "power_in"))
      (node (ref "X102") (pin "1") (pinfunction "VCC_1") (pintype "passive"))
    )
    (net (code "177") (name "VDD") (class "Default")
      (node (ref "C53") (pin "2+") (pinfunction "+_2+") (pintype "passive"))
      (node (ref "C54") (pin "2") (pinfunction "2_2") (pintype "passive"))
      (node (ref "C61") (pin "2") (pinfunction "2_2") (pintype "passive"))
      (node (ref "L8") (pin "2") (pinfunction "2_2") (pintype "passive"))
      (node (ref "M1") (pin "23") (pinfunction "BAT_IN_23") (pintype "power_in"))
    )
    (net (code "178") (name "VDD_IO") (class "Default")
      (node (ref "C60") (pin "2") (pinfunction "2_2") (pintype "passive"))
      (node (ref "M1") (pin "25") (pinfunction "VDD_IO_25") (pintype "power_in"))
    )
    (net (code "179") (name "unconnected-(M1-AOHPL-Pad8)") (class "Default")
      (node (ref "M1") (pin "8") (pinfunction "AOHPL_8") (pintype "output"))
    )
    (net (code "180") (name "unconnected-(M1-AOHPM-Pad7)") (class "Default")
      (node (ref "M1") (pin "7") (pinfunction "AOHPM_7") (pintype "output"))
    )
    (net (code "181") (name "unconnected-(M1-AOHPR-Pad6)") (class "Default")
      (node (ref "M1") (pin "6") (pinfunction "AOHPR_6") (pintype "output"))
    )
    (net (code "182") (name "unconnected-(M1-DMIC1_L-Pad19)") (class "Default")
      (node (ref "M1") (pin "19") (pinfunction "DMIC1_L_19") (pintype "input"))
    )
    (net (code "183") (name "unconnected-(M1-DMIC1_R-Pad18)") (class "Default")
      (node (ref "M1") (pin "18") (pinfunction "DMIC1_R_18") (pintype "input"))
    )
    (net (code "184") (name "unconnected-(M1-DMIC_CLK-Pad17)") (class "Default")
      (node (ref "M1") (pin "17") (pinfunction "DMIC_CLK_17") (pintype "output"))
    )
    (net (code "185") (name "unconnected-(M1-DR1-Pad1)") (class "Default")
      (node (ref "M1") (pin "1") (pinfunction "DR1_1") (pintype "input"))
    )
    (net (code "186") (name "unconnected-(M1-DT1-Pad4)") (class "Default")
      (node (ref "M1") (pin "4") (pinfunction "DT1_4") (pintype "output"))
    )
    (net (code "187") (name "unconnected-(M1-LED1-Pad32)") (class "Default")
      (node (ref "M1") (pin "32") (pinfunction "LED1_32") (pintype "input"))
    )
    (net (code "188") (name "unconnected-(M1-LED2-Pad34)") (class "Default")
      (node (ref "M1") (pin "34") (pinfunction "LED2_34") (pintype "input"))
    )
    (net (code "189") (name "unconnected-(M1-MCLK1-Pad5)") (class "Default")
      (node (ref "M1") (pin "5") (pinfunction "MCLK1_5") (pintype "output"))
    )
    (net (code "190") (name "unconnected-(M1-MICN1-Pad13)") (class "Default")
      (node (ref "M1") (pin "13") (pinfunction "MICN1_13") (pintype "input"))
    )
    (net (code "191") (name "unconnected-(M1-MICN2-Pad9)") (class "Default")
      (node (ref "M1") (pin "9") (pinfunction "MICN2_9") (pintype "input"))
    )
    (net (code "192") (name "unconnected-(M1-MICP1-Pad14)") (class "Default")
      (node (ref "M1") (pin "14") (pinfunction "MICP1_14") (pintype "input"))
    )
    (net (code "193") (name "unconnected-(M1-MICP2-Pad10)") (class "Default")
      (node (ref "M1") (pin "10") (pinfunction "MICP2_10") (pintype "input"))
    )
    (net (code "194") (name "unconnected-(M1-P0_0-Pad49)") (class "Default")
      (node (ref "M1") (pin "49") (pinfunction "P0_0_49") (pintype "bidirectional"))
    )
    (net (code "195") (name "unconnected-(M1-P0_1-Pad44)") (class "Default")
      (node (ref "M1") (pin "44") (pinfunction "P0_1_44") (pintype "bidirectional"))
    )
    (net (code "196") (name "unconnected-(M1-P0_2-Pad33)") (class "Default")
      (node (ref "M1") (pin "33") (pinfunction "P0_2_33") (pintype "bidirectional"))
    )
    (net (code "197") (name "unconnected-(M1-P0_3-Pad38)") (class "Default")
      (node (ref "M1") (pin "38") (pinfunction "P0_3_38") (pintype "bidirectional"))
    )
    (net (code "198") (name "unconnected-(M1-P0_5-Pad40)") (class "Default")
      (node (ref "M1") (pin "40") (pinfunction "P0_5_40") (pintype "bidirectional"))
    )
    (net (code "199") (name "unconnected-(M1-P0_6-Pad35)") (class "Default")
      (node (ref "M1") (pin "35") (pinfunction "P0_6_35") (pintype "bidirectional"))
    )
    (net (code "200") (name "unconnected-(M1-P0_7-Pad45)") (class "Default")
      (node (ref "M1") (pin "45") (pinfunction "P0_7_45") (pintype "bidirectional"))
    )
    (net (code "201") (name "unconnected-(M1-P1_2-Pad46)") (class "Default")
      (node (ref "M1") (pin "46") (pinfunction "P1_2_46") (pintype "bidirectional"))
    )
    (net (code "202") (name "unconnected-(M1-P1_3-Pad47)") (class "Default")
      (node (ref "M1") (pin "47") (pinfunction "P1_3_47") (pintype "bidirectional"))
    )
    (net (code "203") (name "unconnected-(M1-P1_6-Pad41)") (class "Default")
      (node (ref "M1") (pin "41") (pinfunction "P1_6_41") (pintype "bidirectional"))
    )
    (net (code "204") (name "unconnected-(M1-P2_3-Pad42)") (class "Default")
      (node (ref "M1") (pin "42") (pinfunction "P2_3_42") (pintype "bidirectional"))
    )
    (net (code "205") (name "unconnected-(M1-P2_7-Pad39)") (class "Default")
      (node (ref "M1") (pin "39") (pinfunction "P2_7_39") (pintype "bidirectional"))
    )
    (net (code "206") (name "unconnected-(M1-RFS1-Pad2)") (class "Default")
      (node (ref "M1") (pin "2") (pinfunction "RFS1_2") (pintype "bidirectional"))
    )
    (net (code "207") (name "unconnected-(M1-SCLK1-Pad3)") (class "Default")
      (node (ref "M1") (pin "3") (pinfunction "SCLK1_3") (pintype "bidirectional"))
    )
    (net (code "208") (name "unconnected-(M1-SK1_AMB_DET-Pad27)") (class "Default")
      (node (ref "M1") (pin "27") (pinfunction "SK1_AMB_DET_27") (pintype "input"))
    )
    (net (code "209") (name "unconnected-(M1-SK2_KEY_AD-Pad28)") (class "Default")
      (node (ref "M1") (pin "28") (pinfunction "SK2_KEY_AD_28") (pintype "input"))
    )
    (net (code "210") (name "unconnected-(N101-SCX-Pad3)") (class "Default")
      (node (ref "N101") (pin "3") (pinfunction "SCX_3") (pintype "bidirectional"))
    )
    (net (code "211") (name "unconnected-(N101-SDO-Pad1)") (class "Default")
      (node (ref "N101") (pin "1") (pinfunction "SDO_1") (pintype "bidirectional"))
    )
    (net (code "212") (name "unconnected-(N101-SDX-Pad2)") (class "Default")
      (node (ref "N101") (pin "2") (pinfunction "SDX_2") (pintype "bidirectional"))
    )
    (net (code "213") (name "unconnected-(X302-CC1-PadA5)") (class "Default")
      (node (ref "X302") (pin "A5") (pinfunction "CC1_A5") (pintype "bidirectional"))
    )
    (net (code "214") (name "unconnected-(X302-CC2-PadB5)") (class "Default")
      (node (ref "X302") (pin "B5") (pinfunction "CC2_B5") (pintype "bidirectional"))
    )
    (net (code "215") (name "unconnected-(X302-DN1-PadA7)") (class "Default")
      (node (ref "X302") (pin "A7") (pinfunction "DN1_A7") (pintype "bidirectional"))
    )
    (net (code "216") (name "unconnected-(X302-DN2-PadB7)") (class "Default")
      (node (ref "X302") (pin "B7") (pinfunction "DN2_B7") (pintype "bidirectional"))
    )
    (net (code "217") (name "unconnected-(X302-DP1-PadA6)") (class "Default")
      (node (ref "X302") (pin "A6") (pinfunction "DP1_A6") (pintype "bidirectional"))
    )
    (net (code "218") (name "unconnected-(X302-DP2-PadB6)") (class "Default")
      (node (ref "X302") (pin "B6") (pinfunction "DP2_B6") (pintype "bidirectional"))
    )
    (net (code "219") (name "unconnected-(X302-SBU1-PadA8)") (class "Default")
      (node (ref "X302") (pin "A8") (pinfunction "SBU1_A8") (pintype "bidirectional"))
    )
    (net (code "220") (name "unconnected-(X302-SBU2-PadB8)") (class "Default")
      (node (ref "X302") (pin "B8") (pinfunction "SBU2_B8") (pintype "bidirectional"))
    )
    (net (code "221") (name "unconnected-(X302-SSRXN1-PadB10)") (class "Default")
      (node (ref "X302") (pin "B10") (pinfunction "SSRXN1_B10") (pintype "bidirectional"))
    )
    (net (code "222") (name "unconnected-(X302-SSRXN2-PadA10)") (class "Default")
      (node (ref "X302") (pin "A10") (pinfunction "SSRXN2_A10") (pintype "bidirectional"))
    )
    (net (code "223") (name "unconnected-(X302-SSRXP1-PadB11)") (class "Default")
      (node (ref "X302") (pin "B11") (pinfunction "SSRXP1_B11") (pintype "bidirectional"))
    )
    (net (code "224") (name "unconnected-(X302-SSRXP2-PadA11)") (class "Default")
      (node (ref "X302") (pin "A11") (pinfunction "SSRXP2_A11") (pintype "bidirectional"))
    )
    (net (code "225") (name "unconnected-(X302-SSTXN1-PadA3)") (class "Default")
      (node (ref "X302") (pin "A3") (pinfunction "SSTXN1_A3") (pintype "bidirectional"))
    )
    (net (code "226") (name "unconnected-(X302-SSTXN2-PadB3)") (class "Default")
      (node (ref "X302") (pin "B3") (pinfunction "SSTXN2_B3") (pintype "bidirectional"))
    )
    (net (code "227") (name "unconnected-(X302-SSTXP1-PadA2)") (class "Default")
      (node (ref "X302") (pin "A2") (pinfunction "SSTXP1_A2") (pintype "bidirectional"))
    )
    (net (code "228") (name "unconnected-(X302-SSTXP2-PadB2)") (class "Default")
      (node (ref "X302") (pin "B2") (pinfunction "SSTXP2_B2") (pintype "bidirectional"))
    )
    (net (code "229") (name "~{INT1}_PC2") (class "Default")
      (node (ref "N101") (pin "4") (pinfunction "~{INT1}_4") (pintype "bidirectional"))
      (node (ref "U101") (pin "18") (pinfunction "PC2_18") (pintype "bidirectional"))
    )
    (net (code "230") (name "~{INT2}_PC3") (class "Default")
      (node (ref "N101") (pin "9") (pinfunction "~{INT2}_9") (pintype "bidirectional"))
      (node (ref "U101") (pin "19") (pinfunction "PC3_19") (pintype "bidirectional"))
    )
    (net (code "231") (name "~{SS}_PE0") (class "Default")
      (node (ref "N101") (pin "12") (pinfunction "CS_12") (pintype "bidirectional"))
      (node (ref "U101") (pin "30") (pinfunction "PD4_30") (pintype "bidirectional"))
    )
  )
)
